# M1705B.net
KiCad netlist of a schematic drawn in EAGLE
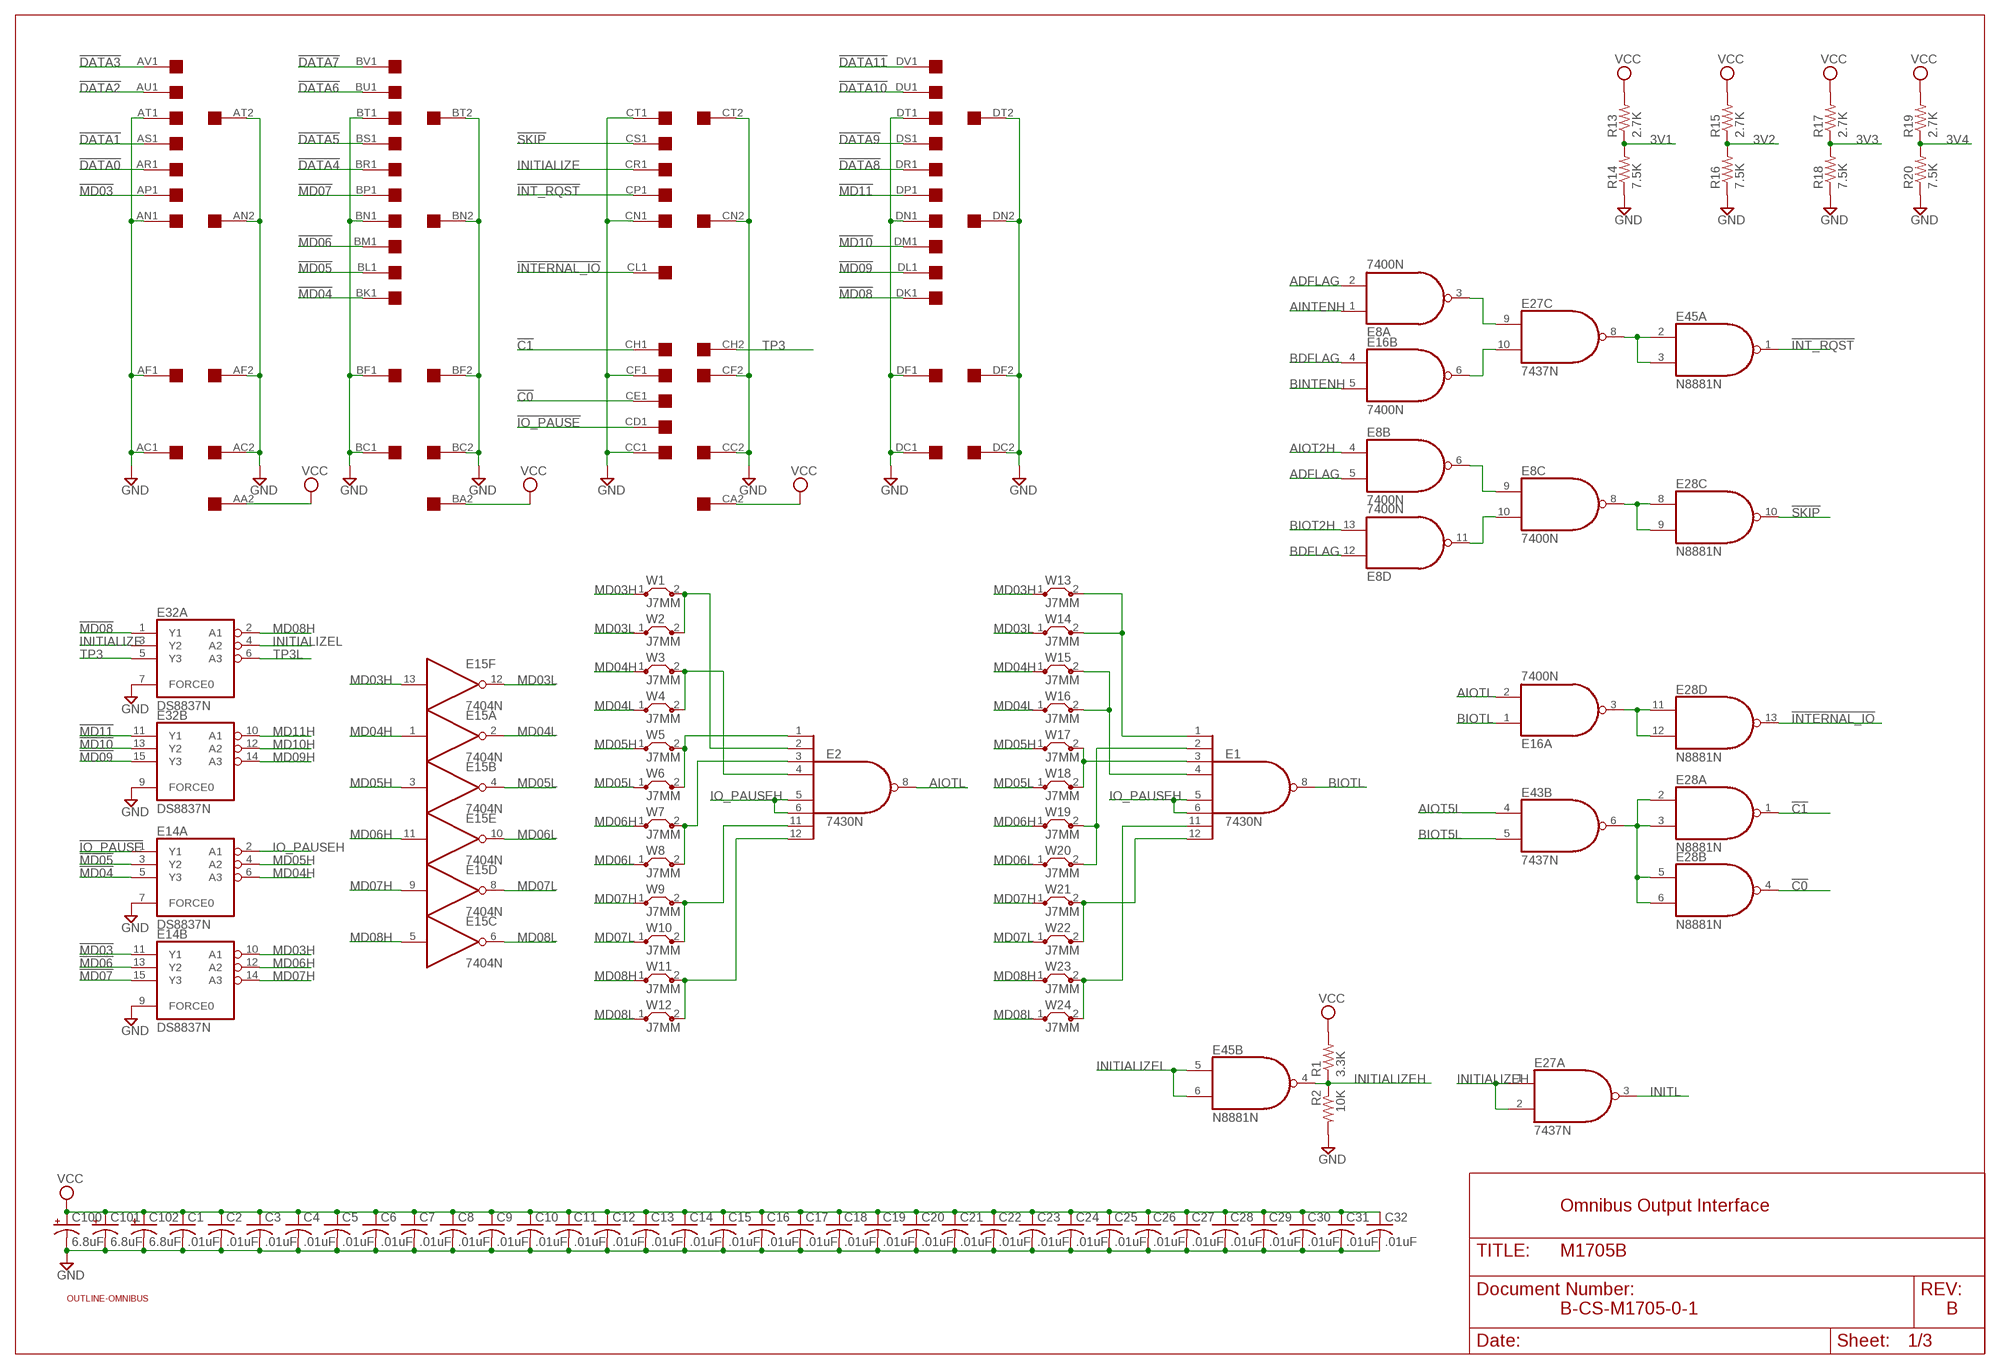
[diagram p0: schematic, sheet 1]
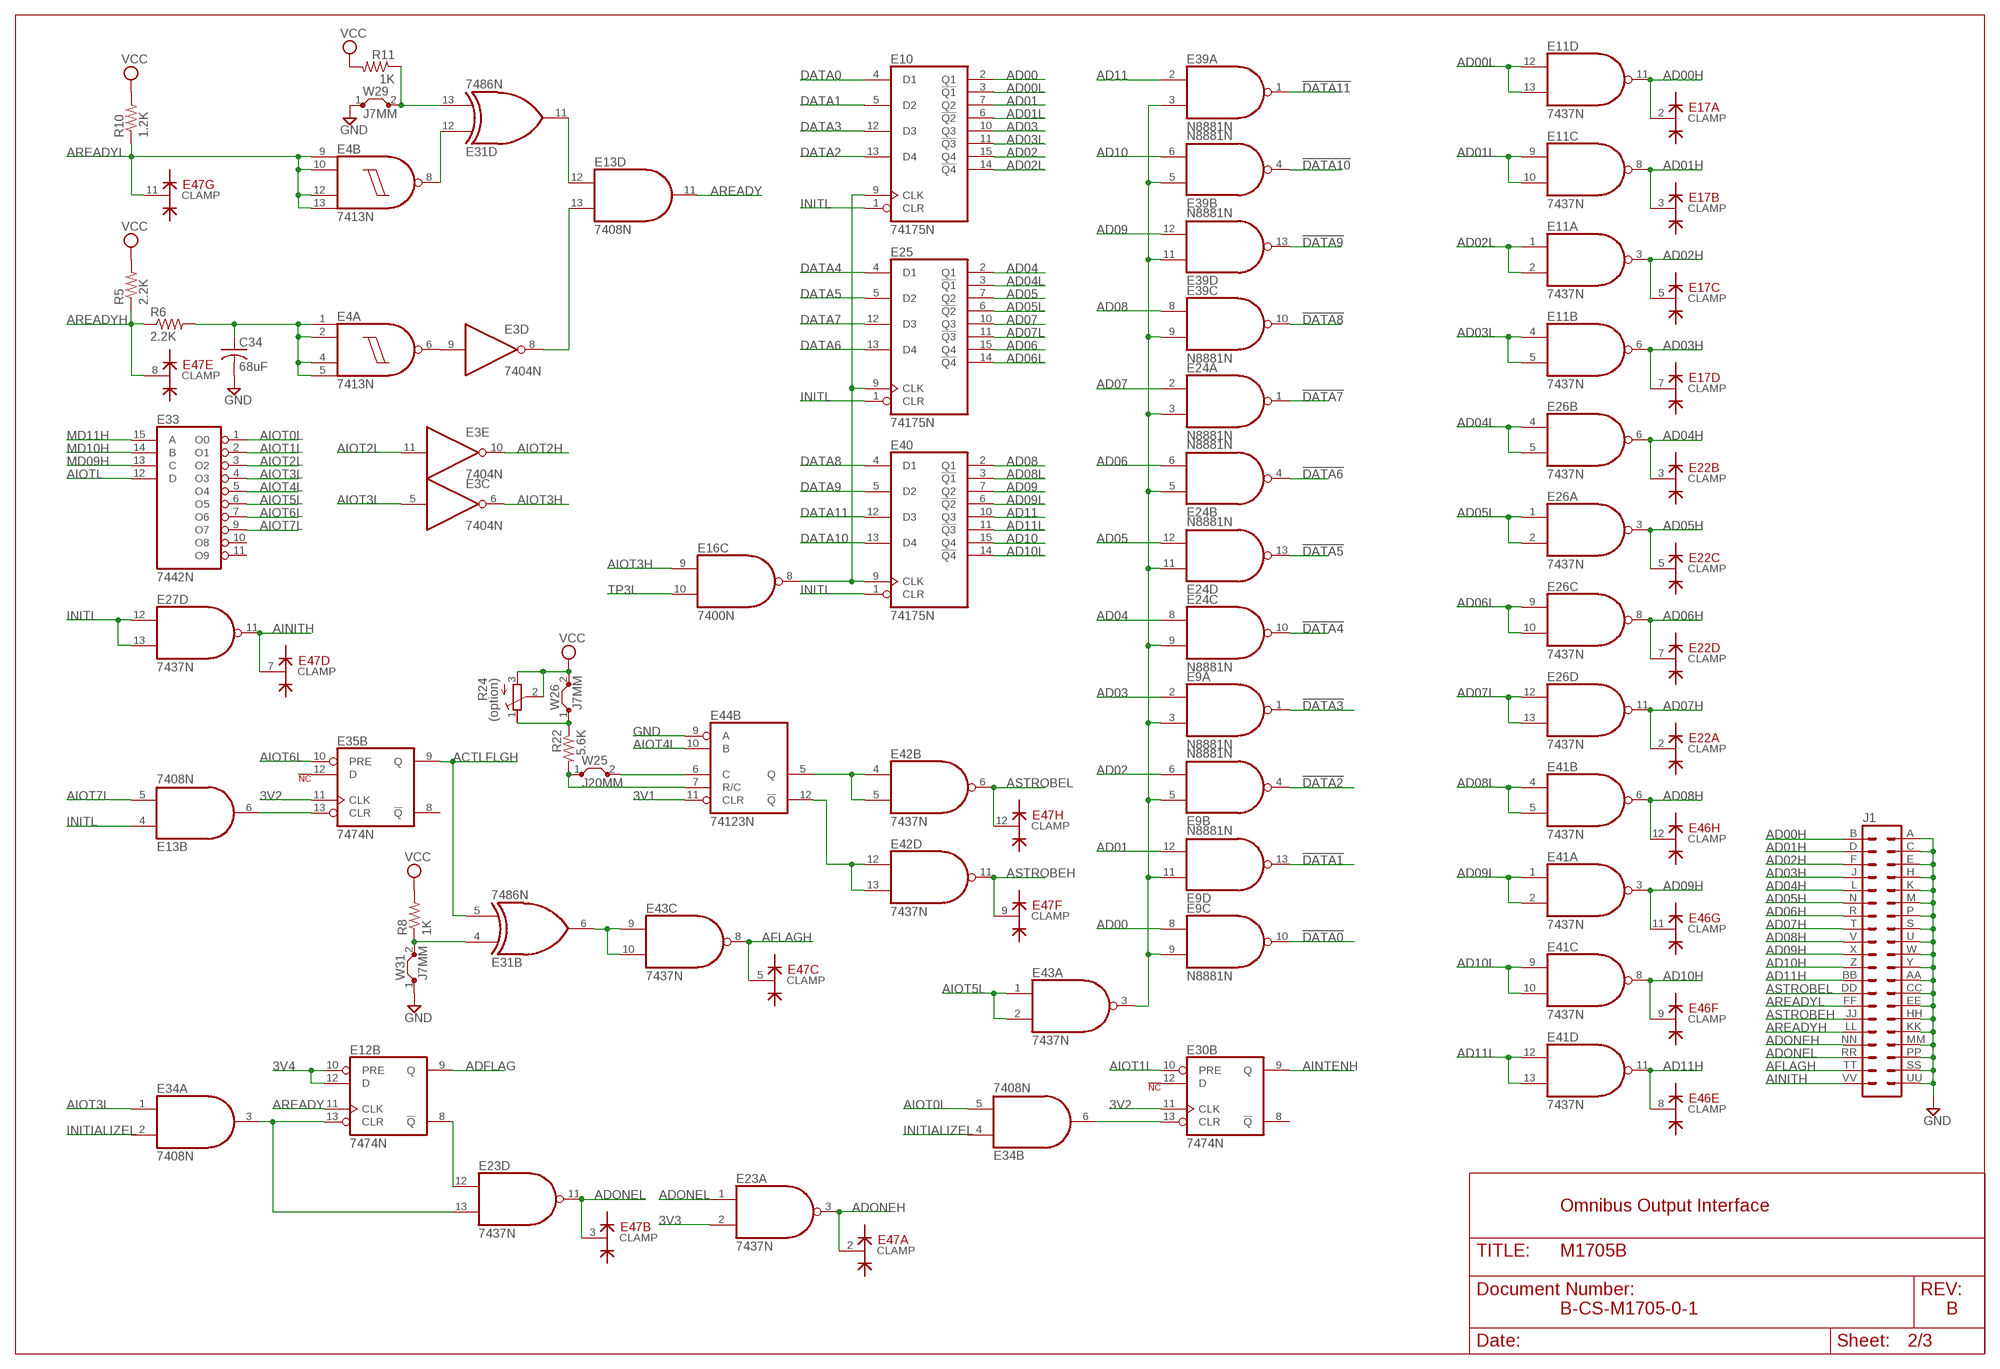
[diagram p1: schematic, sheet 2]
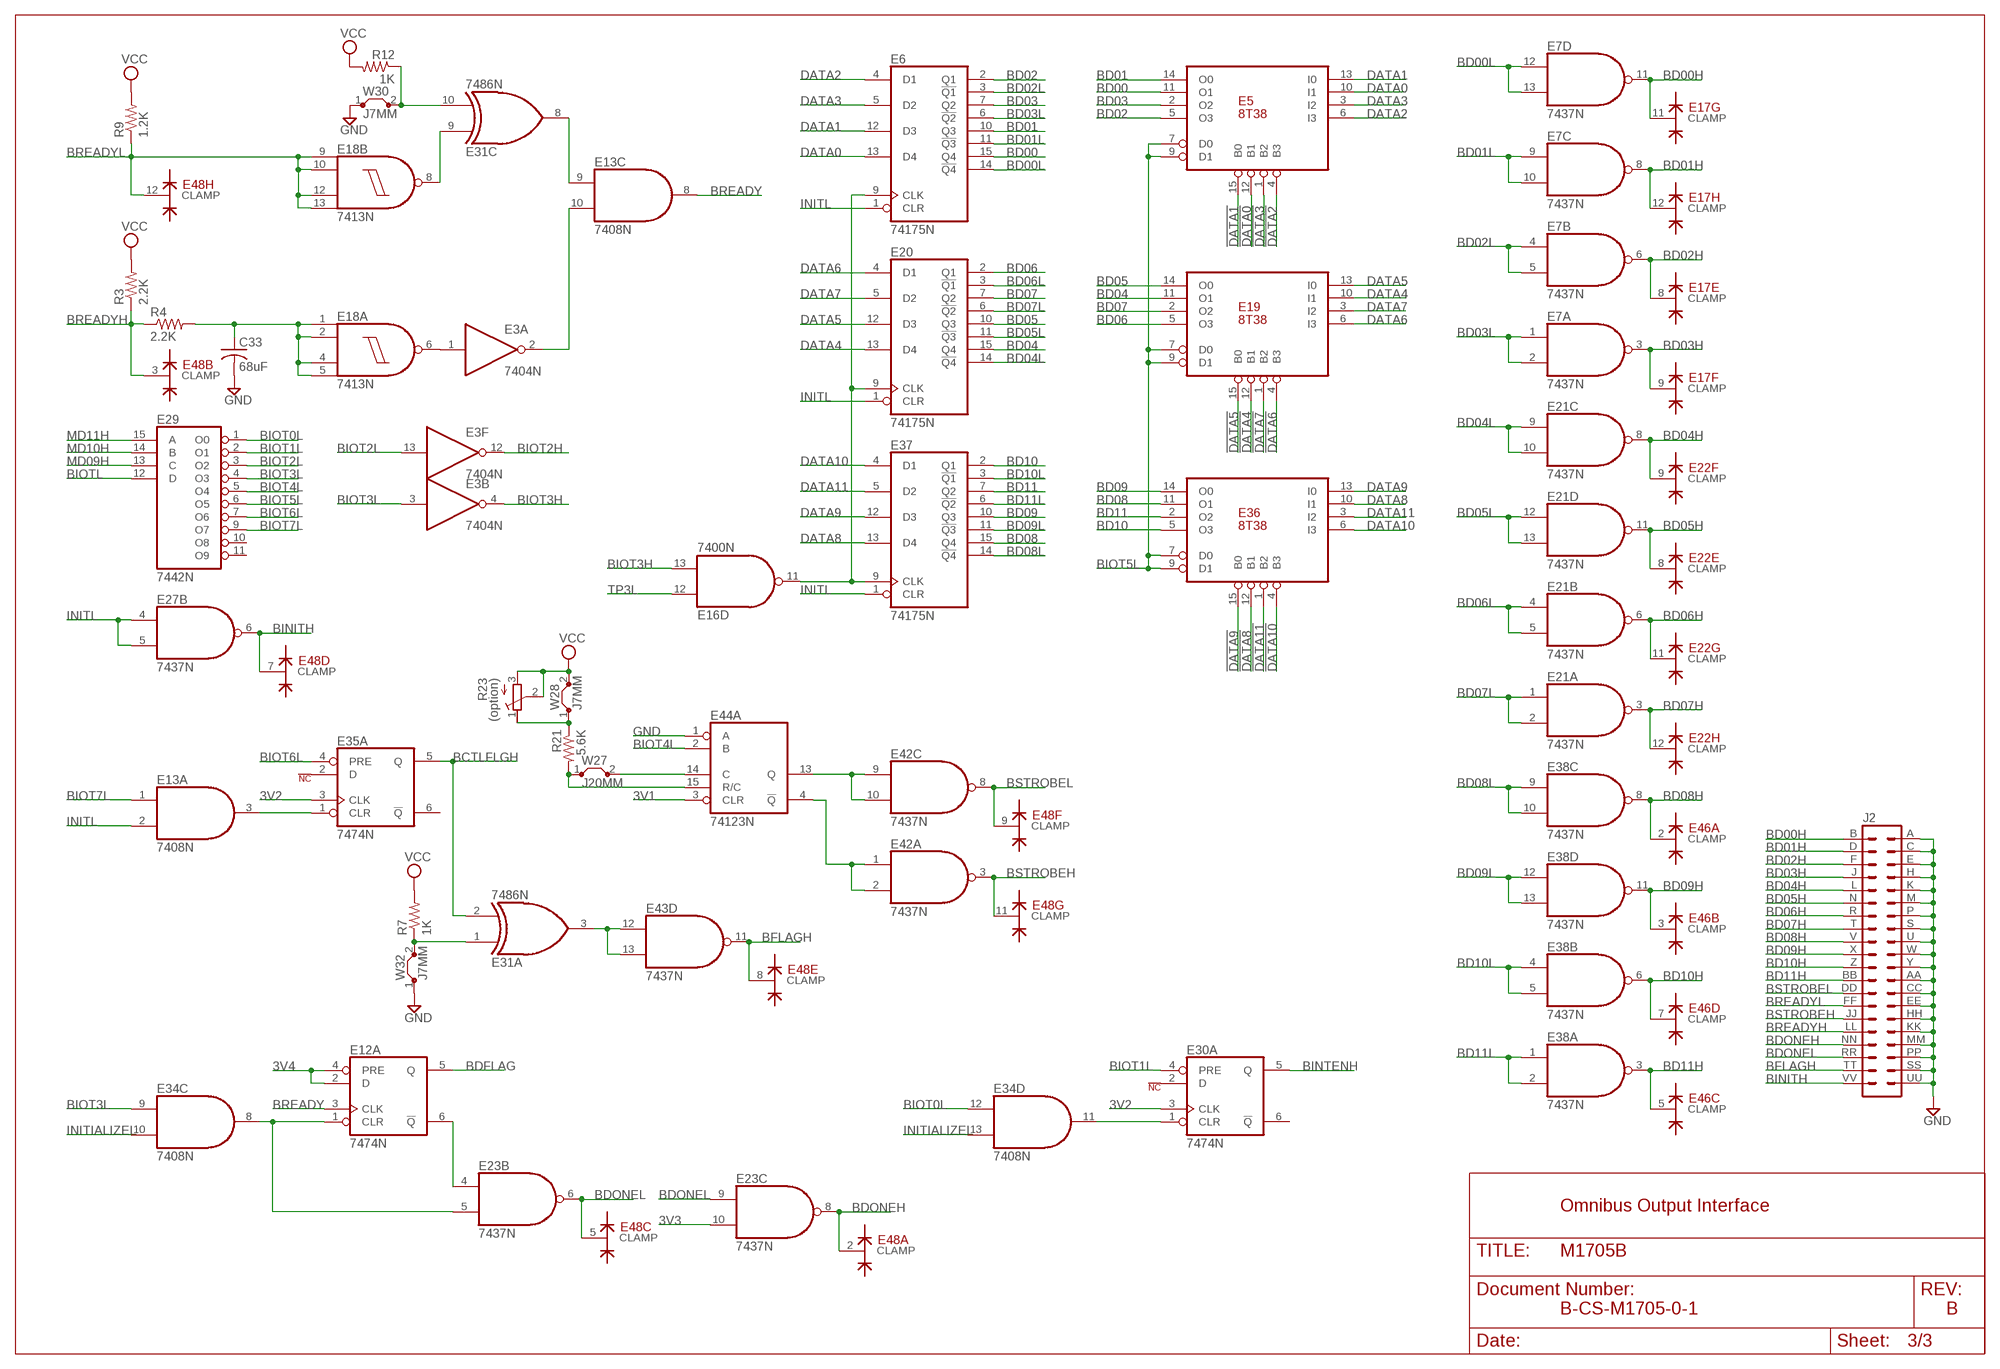
[diagram p2: schematic, sheet 3]

(export (version "E")
  (design (tool "Eeschema 10.0.6"))
  (components
    (comp (ref "C34")
      (value "68uF")
      (footprint "eagle-import:C102-043X133")
      (libsource (lib "eagle-import") (part "C-US102-043X133"))
    )
    (comp (ref "E3")
      (value "7404N")
      (footprint "eagle-import:DIL14")
      (libsource (lib "eagle-import") (part "7404N"))
    )
    (comp (ref "E4")
      (value "7413N")
      (footprint "eagle-import:DIL14")
      (libsource (lib "eagle-import") (part "7413N"))
    )
    (comp (ref "E9")
      (value "N8881N")
      (footprint "eagle-import:DIL14")
      (libsource (lib "eagle-import") (part "N8881N"))
    )
    (comp (ref "E10")
      (value "74175N")
      (footprint "eagle-import:DIL16")
      (libsource (lib "eagle-import") (part "74175N"))
    )
    (comp (ref "E11")
      (value "7437N")
      (footprint "eagle-import:DIL14")
      (libsource (lib "eagle-import") (part "7437N"))
    )
    (comp (ref "E12")
      (value "7474N")
      (footprint "eagle-import:DIL14")
      (libsource (lib "eagle-import") (part "7474NS"))
    )
    (comp (ref "E13")
      (value "7408N")
      (footprint "eagle-import:DIL14")
      (libsource (lib "eagle-import") (part "7408NLS"))
    )
    (comp (ref "E16")
      (value "7400N")
      (footprint "eagle-import:DIL14")
      (libsource (lib "eagle-import") (part "7400N"))
    )
    (comp (ref "E17")
      (value "DEC2501")
      (footprint "eagle-import:DIL14")
      (libsource (lib "eagle-import") (part "DEC2501"))
    )
    (comp (ref "E22")
      (value "DEC2501")
      (footprint "eagle-import:DIL14")
      (libsource (lib "eagle-import") (part "DEC2501"))
    )
    (comp (ref "E23")
      (value "7437N")
      (footprint "eagle-import:DIL14")
      (libsource (lib "eagle-import") (part "7437N"))
    )
    (comp (ref "E24")
      (value "N8881N")
      (footprint "eagle-import:DIL14")
      (libsource (lib "eagle-import") (part "N8881N"))
    )
    (comp (ref "E25")
      (value "74175N")
      (footprint "eagle-import:DIL16")
      (libsource (lib "eagle-import") (part "74175N"))
    )
    (comp (ref "E26")
      (value "7437N")
      (footprint "eagle-import:DIL14")
      (libsource (lib "eagle-import") (part "7437N"))
    )
    (comp (ref "E27")
      (value "7437N")
      (footprint "eagle-import:DIL14")
      (libsource (lib "eagle-import") (part "7437N"))
    )
    (comp (ref "E30")
      (value "7474N")
      (footprint "eagle-import:DIL14")
      (libsource (lib "eagle-import") (part "7474NS"))
    )
    (comp (ref "E31")
      (value "7486N")
      (footprint "eagle-import:DIL14")
      (libsource (lib "eagle-import") (part "7486N"))
    )
    (comp (ref "E33")
      (value "7442N")
      (footprint "eagle-import:DIL16")
      (libsource (lib "eagle-import") (part "7442NLS"))
    )
    (comp (ref "E34")
      (value "7408N")
      (footprint "eagle-import:DIL14")
      (libsource (lib "eagle-import") (part "7408NLS"))
    )
    (comp (ref "E35")
      (value "7474N")
      (footprint "eagle-import:DIL14")
      (libsource (lib "eagle-import") (part "7474NS"))
    )
    (comp (ref "E39")
      (value "N8881N")
      (footprint "eagle-import:DIL14")
      (libsource (lib "eagle-import") (part "N8881N"))
    )
    (comp (ref "E40")
      (value "74175N")
      (footprint "eagle-import:DIL16")
      (libsource (lib "eagle-import") (part "74175N"))
    )
    (comp (ref "E41")
      (value "7437N")
      (footprint "eagle-import:DIL14")
      (libsource (lib "eagle-import") (part "7437N"))
    )
    (comp (ref "E42")
      (value "7437N")
      (footprint "eagle-import:DIL14")
      (libsource (lib "eagle-import") (part "7437N"))
    )
    (comp (ref "E43")
      (value "7437N")
      (footprint "eagle-import:DIL14")
      (libsource (lib "eagle-import") (part "7437N"))
    )
    (comp (ref "E44")
      (value "74123N")
      (footprint "eagle-import:DIL16")
      (libsource (lib "eagle-import") (part "74123N"))
    )
    (comp (ref "E46")
      (value "DEC2501")
      (footprint "eagle-import:DIL14")
      (libsource (lib "eagle-import") (part "DEC2501"))
    )
    (comp (ref "E47")
      (value "DEC2501")
      (footprint "eagle-import:DIL14")
      (libsource (lib "eagle-import") (part "DEC2501"))
    )
    (comp (ref "J1")
      (value "DEC40PINH")
      (footprint "eagle-import:DEC40PINH")
      (libsource (lib "eagle-import") (part "DEC40PINH"))
    )
    (comp (ref "R5")
      (value "2.2K")
      (footprint "eagle-import:0207_10")
      (libsource (lib "eagle-import") (part "R-US_0207/10"))
    )
    (comp (ref "R6")
      (value "2.2K")
      (footprint "eagle-import:0207_10")
      (libsource (lib "eagle-import") (part "R-US_0207/10"))
    )
    (comp (ref "R8")
      (value "1K")
      (footprint "eagle-import:0207_10")
      (libsource (lib "eagle-import") (part "R-US_0207/10"))
    )
    (comp (ref "R10")
      (value "1.2K")
      (footprint "eagle-import:0207_10")
      (libsource (lib "eagle-import") (part "R-US_0207/10"))
    )
    (comp (ref "R11")
      (value "1K")
      (footprint "eagle-import:0207_10")
      (libsource (lib "eagle-import") (part "R-US_0207/10"))
    )
    (comp (ref "R22")
      (value "5.6K")
      (footprint "eagle-import:0207_10")
      (libsource (lib "eagle-import") (part "R-US_0207/10"))
    )
    (comp (ref "R24")
      (value "(option)")
      (footprint "eagle-import:3006Y")
      (libsource (lib "eagle-import") (part "275P"))
    )
    (comp (ref "W25")
      (value "J20MM")
      (footprint "eagle-import:20")
      (libsource (lib "eagle-import") (part "J20MM"))
    )
    (comp (ref "W26")
      (value "J7MM")
      (footprint "eagle-import:07")
      (libsource (lib "eagle-import") (part "J7MM"))
    )
    (comp (ref "W29")
      (value "J7MM")
      (footprint "eagle-import:07")
      (libsource (lib "eagle-import") (part "J7MM"))
    )
    (comp (ref "W31")
      (value "J7MM")
      (footprint "eagle-import:07")
      (libsource (lib "eagle-import") (part "J7MM"))
    )
    (comp (ref "C33")
      (value "68uF")
      (footprint "eagle-import:C102-043X133")
      (libsource (lib "eagle-import") (part "C-US102-043X133"))
    )
    (comp (ref "E5")
      (value "8T38")
      (footprint "eagle-import:DIL16")
      (libsource (lib "eagle-import") (part "DS8641N"))
    )
    (comp (ref "E6")
      (value "74175N")
      (footprint "eagle-import:DIL16")
      (libsource (lib "eagle-import") (part "74175N"))
    )
    (comp (ref "E7")
      (value "7437N")
      (footprint "eagle-import:DIL14")
      (libsource (lib "eagle-import") (part "7437N"))
    )
    (comp (ref "E18")
      (value "7413N")
      (footprint "eagle-import:DIL14")
      (libsource (lib "eagle-import") (part "7413N"))
    )
    (comp (ref "E19")
      (value "8T38")
      (footprint "eagle-import:DIL16")
      (libsource (lib "eagle-import") (part "DS8641N"))
    )
    (comp (ref "E20")
      (value "74175N")
      (footprint "eagle-import:DIL16")
      (libsource (lib "eagle-import") (part "74175N"))
    )
    (comp (ref "E21")
      (value "7437N")
      (footprint "eagle-import:DIL14")
      (libsource (lib "eagle-import") (part "7437N"))
    )
    (comp (ref "E29")
      (value "7442N")
      (footprint "eagle-import:DIL16")
      (libsource (lib "eagle-import") (part "7442NLS"))
    )
    (comp (ref "E36")
      (value "8T38")
      (footprint "eagle-import:DIL16")
      (libsource (lib "eagle-import") (part "DS8641N"))
    )
    (comp (ref "E37")
      (value "74175N")
      (footprint "eagle-import:DIL16")
      (libsource (lib "eagle-import") (part "74175N"))
    )
    (comp (ref "E38")
      (value "7437N")
      (footprint "eagle-import:DIL14")
      (libsource (lib "eagle-import") (part "7437N"))
    )
    (comp (ref "E48")
      (value "DEC2501")
      (footprint "eagle-import:DIL14")
      (libsource (lib "eagle-import") (part "DEC2501"))
    )
    (comp (ref "J2")
      (value "DEC40PINH")
      (footprint "eagle-import:DEC40PINH")
      (libsource (lib "eagle-import") (part "DEC40PINH"))
    )
    (comp (ref "R3")
      (value "2.2K")
      (footprint "eagle-import:0207_10")
      (libsource (lib "eagle-import") (part "R-US_0207/10"))
    )
    (comp (ref "R4")
      (value "2.2K")
      (footprint "eagle-import:0207_10")
      (libsource (lib "eagle-import") (part "R-US_0207/10"))
    )
    (comp (ref "R7")
      (value "1K")
      (footprint "eagle-import:0207_10")
      (libsource (lib "eagle-import") (part "R-US_0207/10"))
    )
    (comp (ref "R9")
      (value "1.2K")
      (footprint "eagle-import:0207_10")
      (libsource (lib "eagle-import") (part "R-US_0207/10"))
    )
    (comp (ref "R12")
      (value "1K")
      (footprint "eagle-import:0207_10")
      (libsource (lib "eagle-import") (part "R-US_0207/10"))
    )
    (comp (ref "R21")
      (value "5.6K")
      (footprint "eagle-import:0207_10")
      (libsource (lib "eagle-import") (part "R-US_0207/10"))
    )
    (comp (ref "R23")
      (value "(option)")
      (footprint "eagle-import:3006Y")
      (libsource (lib "eagle-import") (part "275P"))
    )
    (comp (ref "W27")
      (value "J20MM")
      (footprint "eagle-import:20")
      (libsource (lib "eagle-import") (part "J20MM"))
    )
    (comp (ref "W28")
      (value "J7MM")
      (footprint "eagle-import:07")
      (libsource (lib "eagle-import") (part "J7MM"))
    )
    (comp (ref "W30")
      (value "J7MM")
      (footprint "eagle-import:07")
      (libsource (lib "eagle-import") (part "J7MM"))
    )
    (comp (ref "W32")
      (value "J7MM")
      (footprint "eagle-import:07")
      (libsource (lib "eagle-import") (part "J7MM"))
    )
    (comp (ref "C1")
      (value ".01uF")
      (footprint "eagle-import:C075-032X103")
      (libsource (lib "eagle-import") (part "C-US075-032X103"))
    )
    (comp (ref "C2")
      (value ".01uF")
      (footprint "eagle-import:C075-032X103")
      (libsource (lib "eagle-import") (part "C-US075-032X103"))
    )
    (comp (ref "C3")
      (value ".01uF")
      (footprint "eagle-import:C075-032X103")
      (libsource (lib "eagle-import") (part "C-US075-032X103"))
    )
    (comp (ref "C4")
      (value ".01uF")
      (footprint "eagle-import:C075-032X103")
      (libsource (lib "eagle-import") (part "C-US075-032X103"))
    )
    (comp (ref "C5")
      (value ".01uF")
      (footprint "eagle-import:C075-032X103")
      (libsource (lib "eagle-import") (part "C-US075-032X103"))
    )
    (comp (ref "C6")
      (value ".01uF")
      (footprint "eagle-import:C075-032X103")
      (libsource (lib "eagle-import") (part "C-US075-032X103"))
    )
    (comp (ref "C7")
      (value ".01uF")
      (footprint "eagle-import:C075-032X103")
      (libsource (lib "eagle-import") (part "C-US075-032X103"))
    )
    (comp (ref "C8")
      (value ".01uF")
      (footprint "eagle-import:C075-032X103")
      (libsource (lib "eagle-import") (part "C-US075-032X103"))
    )
    (comp (ref "C9")
      (value ".01uF")
      (footprint "eagle-import:C075-032X103")
      (libsource (lib "eagle-import") (part "C-US075-032X103"))
    )
    (comp (ref "C10")
      (value ".01uF")
      (footprint "eagle-import:C075-032X103")
      (libsource (lib "eagle-import") (part "C-US075-032X103"))
    )
    (comp (ref "C11")
      (value ".01uF")
      (footprint "eagle-import:C075-032X103")
      (libsource (lib "eagle-import") (part "C-US075-032X103"))
    )
    (comp (ref "C12")
      (value ".01uF")
      (footprint "eagle-import:C075-032X103")
      (libsource (lib "eagle-import") (part "C-US075-032X103"))
    )
    (comp (ref "C13")
      (value ".01uF")
      (footprint "eagle-import:C075-032X103")
      (libsource (lib "eagle-import") (part "C-US075-032X103"))
    )
    (comp (ref "C14")
      (value ".01uF")
      (footprint "eagle-import:C075-032X103")
      (libsource (lib "eagle-import") (part "C-US075-032X103"))
    )
    (comp (ref "C15")
      (value ".01uF")
      (footprint "eagle-import:C075-032X103")
      (libsource (lib "eagle-import") (part "C-US075-032X103"))
    )
    (comp (ref "C16")
      (value ".01uF")
      (footprint "eagle-import:C075-032X103")
      (libsource (lib "eagle-import") (part "C-US075-032X103"))
    )
    (comp (ref "C17")
      (value ".01uF")
      (footprint "eagle-import:C075-032X103")
      (libsource (lib "eagle-import") (part "C-US075-032X103"))
    )
    (comp (ref "C18")
      (value ".01uF")
      (footprint "eagle-import:C075-032X103")
      (libsource (lib "eagle-import") (part "C-US075-032X103"))
    )
    (comp (ref "C19")
      (value ".01uF")
      (footprint "eagle-import:C075-032X103")
      (libsource (lib "eagle-import") (part "C-US075-032X103"))
    )
    (comp (ref "C20")
      (value ".01uF")
      (footprint "eagle-import:C075-032X103")
      (libsource (lib "eagle-import") (part "C-US075-032X103"))
    )
    (comp (ref "C21")
      (value ".01uF")
      (footprint "eagle-import:C075-032X103")
      (libsource (lib "eagle-import") (part "C-US075-032X103"))
    )
    (comp (ref "C22")
      (value ".01uF")
      (footprint "eagle-import:C075-032X103")
      (libsource (lib "eagle-import") (part "C-US075-032X103"))
    )
    (comp (ref "C23")
      (value ".01uF")
      (footprint "eagle-import:C075-032X103")
      (libsource (lib "eagle-import") (part "C-US075-032X103"))
    )
    (comp (ref "C24")
      (value ".01uF")
      (footprint "eagle-import:C075-032X103")
      (libsource (lib "eagle-import") (part "C-US075-032X103"))
    )
    (comp (ref "C25")
      (value ".01uF")
      (footprint "eagle-import:C075-032X103")
      (libsource (lib "eagle-import") (part "C-US075-032X103"))
    )
    (comp (ref "C26")
      (value ".01uF")
      (footprint "eagle-import:C075-032X103")
      (libsource (lib "eagle-import") (part "C-US075-032X103"))
    )
    (comp (ref "C27")
      (value ".01uF")
      (footprint "eagle-import:C075-032X103")
      (libsource (lib "eagle-import") (part "C-US075-032X103"))
    )
    (comp (ref "C28")
      (value ".01uF")
      (footprint "eagle-import:C075-032X103")
      (libsource (lib "eagle-import") (part "C-US075-032X103"))
    )
    (comp (ref "C29")
      (value ".01uF")
      (footprint "eagle-import:C075-032X103")
      (libsource (lib "eagle-import") (part "C-US075-032X103"))
    )
    (comp (ref "C30")
      (value ".01uF")
      (footprint "eagle-import:C075-032X103")
      (libsource (lib "eagle-import") (part "C-US075-032X103"))
    )
    (comp (ref "C31")
      (value ".01uF")
      (footprint "eagle-import:C075-032X103")
      (libsource (lib "eagle-import") (part "C-US075-032X103"))
    )
    (comp (ref "C32")
      (value ".01uF")
      (footprint "eagle-import:C075-032X103")
      (libsource (lib "eagle-import") (part "C-US075-032X103"))
    )
    (comp (ref "C100")
      (value "6.8uF")
      (footprint "eagle-import:E12-8")
      (libsource (lib "eagle-import") (part "CPOL-USE20-8AXIAL"))
    )
    (comp (ref "C101")
      (value "6.8uF")
      (footprint "eagle-import:E12-8")
      (libsource (lib "eagle-import") (part "CPOL-USE20-8AXIAL"))
    )
    (comp (ref "C102")
      (value "6.8uF")
      (footprint "eagle-import:E12-8")
      (libsource (lib "eagle-import") (part "CPOL-USE20-8AXIAL"))
    )
    (comp (ref "E1")
      (value "7430N")
      (footprint "eagle-import:DIL14")
      (libsource (lib "eagle-import") (part "7430N"))
    )
    (comp (ref "E2")
      (value "7430N")
      (footprint "eagle-import:DIL14")
      (libsource (lib "eagle-import") (part "7430N"))
    )
    (comp (ref "E8")
      (value "7400N")
      (footprint "eagle-import:DIL14")
      (libsource (lib "eagle-import") (part "7400N"))
    )
    (comp (ref "E14")
      (value "DS8837N")
      (footprint "eagle-import:DIL16")
      (libsource (lib "eagle-import") (part "DS8837N"))
    )
    (comp (ref "E15")
      (value "7404N")
      (footprint "eagle-import:DIL14")
      (libsource (lib "eagle-import") (part "7404N"))
    )
    (comp (ref "E28")
      (value "N8881N")
      (footprint "eagle-import:DIL14")
      (libsource (lib "eagle-import") (part "N8881N"))
    )
    (comp (ref "E32")
      (value "DS8837N")
      (footprint "eagle-import:DIL16")
      (libsource (lib "eagle-import") (part "DS8837N"))
    )
    (comp (ref "E45")
      (value "N8881N")
      (footprint "eagle-import:DIL14")
      (libsource (lib "eagle-import") (part "N8881N"))
    )
    (comp (ref "R1")
      (value "3.3K")
      (footprint "eagle-import:0207_10")
      (libsource (lib "eagle-import") (part "R-US_0207/10"))
    )
    (comp (ref "R2")
      (value "10K")
      (footprint "eagle-import:0207_10")
      (libsource (lib "eagle-import") (part "R-US_0207/10"))
    )
    (comp (ref "R13")
      (value "2.7K")
      (footprint "eagle-import:0207_10")
      (libsource (lib "eagle-import") (part "R-US_0207/10"))
    )
    (comp (ref "R14")
      (value "7.5K")
      (footprint "eagle-import:0207_10")
      (libsource (lib "eagle-import") (part "R-US_0207/10"))
    )
    (comp (ref "R15")
      (value "2.7K")
      (footprint "eagle-import:0207_10")
      (libsource (lib "eagle-import") (part "R-US_0207/10"))
    )
    (comp (ref "R16")
      (value "7.5K")
      (footprint "eagle-import:0207_10")
      (libsource (lib "eagle-import") (part "R-US_0207/10"))
    )
    (comp (ref "R17")
      (value "2.7K")
      (footprint "eagle-import:0207_10")
      (libsource (lib "eagle-import") (part "R-US_0207/10"))
    )
    (comp (ref "R18")
      (value "7.5K")
      (footprint "eagle-import:0207_10")
      (libsource (lib "eagle-import") (part "R-US_0207/10"))
    )
    (comp (ref "R19")
      (value "2.7K")
      (footprint "eagle-import:0207_10")
      (libsource (lib "eagle-import") (part "R-US_0207/10"))
    )
    (comp (ref "R20")
      (value "7.5K")
      (footprint "eagle-import:0207_10")
      (libsource (lib "eagle-import") (part "R-US_0207/10"))
    )
    (comp (ref "U$2")
      (value "QUAD")
      (footprint "eagle-import:EDGE-CON8")
      (libsource (lib "eagle-import") (part "QUAD"))
    )
    (comp (ref "U$4")
      (value "OUTLINE-OMNIBUS")
      (footprint "eagle-import:OMNIBUS")
      (libsource (lib "eagle-import") (part "OUTLINE-OMNIBUS"))
    )
    (comp (ref "W1")
      (value "J7MM")
      (footprint "eagle-import:07")
      (libsource (lib "eagle-import") (part "J7MM"))
    )
    (comp (ref "W2")
      (value "J7MM")
      (footprint "eagle-import:07")
      (libsource (lib "eagle-import") (part "J7MM"))
    )
    (comp (ref "W3")
      (value "J7MM")
      (footprint "eagle-import:07")
      (libsource (lib "eagle-import") (part "J7MM"))
    )
    (comp (ref "W4")
      (value "J7MM")
      (footprint "eagle-import:07")
      (libsource (lib "eagle-import") (part "J7MM"))
    )
    (comp (ref "W5")
      (value "J7MM")
      (footprint "eagle-import:07")
      (libsource (lib "eagle-import") (part "J7MM"))
    )
    (comp (ref "W6")
      (value "J7MM")
      (footprint "eagle-import:07")
      (libsource (lib "eagle-import") (part "J7MM"))
    )
    (comp (ref "W7")
      (value "J7MM")
      (footprint "eagle-import:07")
      (libsource (lib "eagle-import") (part "J7MM"))
    )
    (comp (ref "W8")
      (value "J7MM")
      (footprint "eagle-import:07")
      (libsource (lib "eagle-import") (part "J7MM"))
    )
    (comp (ref "W9")
      (value "J7MM")
      (footprint "eagle-import:07")
      (libsource (lib "eagle-import") (part "J7MM"))
    )
    (comp (ref "W10")
      (value "J7MM")
      (footprint "eagle-import:07")
      (libsource (lib "eagle-import") (part "J7MM"))
    )
    (comp (ref "W11")
      (value "J7MM")
      (footprint "eagle-import:07")
      (libsource (lib "eagle-import") (part "J7MM"))
    )
    (comp (ref "W12")
      (value "J7MM")
      (footprint "eagle-import:07")
      (libsource (lib "eagle-import") (part "J7MM"))
    )
    (comp (ref "W13")
      (value "J7MM")
      (footprint "eagle-import:07")
      (libsource (lib "eagle-import") (part "J7MM"))
    )
    (comp (ref "W14")
      (value "J7MM")
      (footprint "eagle-import:07")
      (libsource (lib "eagle-import") (part "J7MM"))
    )
    (comp (ref "W15")
      (value "J7MM")
      (footprint "eagle-import:07")
      (libsource (lib "eagle-import") (part "J7MM"))
    )
    (comp (ref "W16")
      (value "J7MM")
      (footprint "eagle-import:07")
      (libsource (lib "eagle-import") (part "J7MM"))
    )
    (comp (ref "W17")
      (value "J7MM")
      (footprint "eagle-import:07")
      (libsource (lib "eagle-import") (part "J7MM"))
    )
    (comp (ref "W18")
      (value "J7MM")
      (footprint "eagle-import:07")
      (libsource (lib "eagle-import") (part "J7MM"))
    )
    (comp (ref "W19")
      (value "J7MM")
      (footprint "eagle-import:07")
      (libsource (lib "eagle-import") (part "J7MM"))
    )
    (comp (ref "W20")
      (value "J7MM")
      (footprint "eagle-import:07")
      (libsource (lib "eagle-import") (part "J7MM"))
    )
    (comp (ref "W21")
      (value "J7MM")
      (footprint "eagle-import:07")
      (libsource (lib "eagle-import") (part "J7MM"))
    )
    (comp (ref "W22")
      (value "J7MM")
      (footprint "eagle-import:07")
      (libsource (lib "eagle-import") (part "J7MM"))
    )
    (comp (ref "W23")
      (value "J7MM")
      (footprint "eagle-import:07")
      (libsource (lib "eagle-import") (part "J7MM"))
    )
    (comp (ref "W24")
      (value "J7MM")
      (footprint "eagle-import:07")
      (libsource (lib "eagle-import") (part "J7MM"))
    )
  )
  (nets
    (net (code "1") (name "3V1") (class "Default")
      (node (ref "E44") (pin "11") (pinfunction "CLR_11") (pintype "input"))
      (node (ref "E44") (pin "3") (pinfunction "CLR_3") (pintype "input"))
      (node (ref "R13") (pin "1") (pinfunction "1_1") (pintype "passive"))
      (node (ref "R14") (pin "2") (pinfunction "2_2") (pintype "passive"))
    )
    (net (code "2") (name "3V2") (class "Default")
      (node (ref "E30") (pin "11") (pinfunction "CLK_11") (pintype "input"))
      (node (ref "E30") (pin "3") (pinfunction "CLK_3") (pintype "input"))
      (node (ref "E35") (pin "11") (pinfunction "CLK_11") (pintype "input"))
      (node (ref "E35") (pin "3") (pinfunction "CLK_3") (pintype "input"))
      (node (ref "R15") (pin "1") (pinfunction "1_1") (pintype "passive"))
      (node (ref "R16") (pin "2") (pinfunction "2_2") (pintype "passive"))
    )
    (net (code "3") (name "3V3") (class "Default")
      (node (ref "E23") (pin "10") (pinfunction "I1_10") (pintype "input"))
      (node (ref "E23") (pin "2") (pinfunction "I1_2") (pintype "input"))
      (node (ref "R17") (pin "1") (pinfunction "1_1") (pintype "passive"))
      (node (ref "R18") (pin "2") (pinfunction "2_2") (pintype "passive"))
    )
    (net (code "4") (name "3V4") (class "Default")
      (node (ref "E12") (pin "10") (pinfunction "PRE_10") (pintype "input"))
      (node (ref "E12") (pin "12") (pinfunction "D_12") (pintype "input"))
      (node (ref "E12") (pin "2") (pinfunction "D_2") (pintype "input"))
      (node (ref "E12") (pin "4") (pinfunction "PRE_4") (pintype "input"))
      (node (ref "R19") (pin "1") (pinfunction "1_1") (pintype "passive"))
      (node (ref "R20") (pin "2") (pinfunction "2_2") (pintype "passive"))
    )
    (net (code "5") (name "ACTLFLGH") (class "Default")
      (node (ref "E31") (pin "5") (pinfunction "I1_5") (pintype "input"))
      (node (ref "E35") (pin "9") (pinfunction "Q_9") (pintype "output"))
    )
    (net (code "6") (name "AD00") (class "Default")
      (node (ref "E10") (pin "2") (pinfunction "Q1_2") (pintype "output"))
      (node (ref "E9") (pin "8") (pinfunction "I0_8") (pintype "input"))
    )
    (net (code "7") (name "AD00H") (class "Default")
      (node (ref "E11") (pin "11") (pinfunction "O_11") (pintype "output"))
      (node (ref "E17") (pin "2") (pinfunction "CLAMP_2") (pintype "input"))
      (node (ref "J1") (pin "B") (pinfunction "2_B") (pintype "bidirectional"))
    )
    (net (code "8") (name "AD00L") (class "Default")
      (node (ref "E10") (pin "3") (pinfunction "~{Q1}_3") (pintype "output"))
      (node (ref "E11") (pin "12") (pinfunction "I0_12") (pintype "input"))
      (node (ref "E11") (pin "13") (pinfunction "I1_13") (pintype "input"))
    )
    (net (code "9") (name "AD01") (class "Default")
      (node (ref "E10") (pin "7") (pinfunction "Q2_7") (pintype "output"))
      (node (ref "E9") (pin "12") (pinfunction "I1_12") (pintype "input"))
    )
    (net (code "10") (name "AD01H") (class "Default")
      (node (ref "E11") (pin "8") (pinfunction "O_8") (pintype "output"))
      (node (ref "E17") (pin "3") (pinfunction "CLAMP_3") (pintype "input"))
      (node (ref "J1") (pin "D") (pinfunction "4_D") (pintype "bidirectional"))
    )
    (net (code "11") (name "AD01L") (class "Default")
      (node (ref "E10") (pin "6") (pinfunction "~{Q2}_6") (pintype "output"))
      (node (ref "E11") (pin "10") (pinfunction "I1_10") (pintype "input"))
      (node (ref "E11") (pin "9") (pinfunction "I0_9") (pintype "input"))
    )
    (net (code "12") (name "AD02") (class "Default")
      (node (ref "E10") (pin "15") (pinfunction "Q4_15") (pintype "output"))
      (node (ref "E9") (pin "6") (pinfunction "I1_6") (pintype "input"))
    )
    (net (code "13") (name "AD02H") (class "Default")
      (node (ref "E11") (pin "3") (pinfunction "O_3") (pintype "output"))
      (node (ref "E17") (pin "5") (pinfunction "CLAMP_5") (pintype "input"))
      (node (ref "J1") (pin "F") (pinfunction "6_F") (pintype "bidirectional"))
    )
    (net (code "14") (name "AD02L") (class "Default")
      (node (ref "E10") (pin "14") (pinfunction "~{Q4}_14") (pintype "output"))
      (node (ref "E11") (pin "1") (pinfunction "I0_1") (pintype "input"))
      (node (ref "E11") (pin "2") (pinfunction "I1_2") (pintype "input"))
    )
    (net (code "15") (name "AD03") (class "Default")
      (node (ref "E10") (pin "10") (pinfunction "Q3_10") (pintype "output"))
      (node (ref "E9") (pin "2") (pinfunction "I0_2") (pintype "input"))
    )
    (net (code "16") (name "AD03H") (class "Default")
      (node (ref "E11") (pin "6") (pinfunction "O_6") (pintype "output"))
      (node (ref "E17") (pin "7") (pinfunction "CLAMP_7") (pintype "input"))
      (node (ref "J1") (pin "J") (pinfunction "8_J") (pintype "bidirectional"))
    )
    (net (code "17") (name "AD03L") (class "Default")
      (node (ref "E10") (pin "11") (pinfunction "~{Q3}_11") (pintype "output"))
      (node (ref "E11") (pin "4") (pinfunction "I0_4") (pintype "input"))
      (node (ref "E11") (pin "5") (pinfunction "I1_5") (pintype "input"))
    )
    (net (code "18") (name "AD04") (class "Default")
      (node (ref "E24") (pin "8") (pinfunction "I0_8") (pintype "input"))
      (node (ref "E25") (pin "2") (pinfunction "Q1_2") (pintype "output"))
    )
    (net (code "19") (name "AD04H") (class "Default")
      (node (ref "E22") (pin "3") (pinfunction "CLAMP_3") (pintype "input"))
      (node (ref "E26") (pin "6") (pinfunction "O_6") (pintype "output"))
      (node (ref "J1") (pin "L") (pinfunction "10_L") (pintype "bidirectional"))
    )
    (net (code "20") (name "AD04L") (class "Default")
      (node (ref "E25") (pin "3") (pinfunction "~{Q1}_3") (pintype "output"))
      (node (ref "E26") (pin "4") (pinfunction "I0_4") (pintype "input"))
      (node (ref "E26") (pin "5") (pinfunction "I1_5") (pintype "input"))
    )
    (net (code "21") (name "AD05") (class "Default")
      (node (ref "E24") (pin "12") (pinfunction "I1_12") (pintype "input"))
      (node (ref "E25") (pin "7") (pinfunction "Q2_7") (pintype "output"))
    )
    (net (code "22") (name "AD05H") (class "Default")
      (node (ref "E22") (pin "5") (pinfunction "CLAMP_5") (pintype "input"))
      (node (ref "E26") (pin "3") (pinfunction "O_3") (pintype "output"))
      (node (ref "J1") (pin "N") (pinfunction "12_N") (pintype "bidirectional"))
    )
    (net (code "23") (name "AD05L") (class "Default")
      (node (ref "E25") (pin "6") (pinfunction "~{Q2}_6") (pintype "output"))
      (node (ref "E26") (pin "1") (pinfunction "I0_1") (pintype "input"))
      (node (ref "E26") (pin "2") (pinfunction "I1_2") (pintype "input"))
    )
    (net (code "24") (name "AD06") (class "Default")
      (node (ref "E24") (pin "6") (pinfunction "I1_6") (pintype "input"))
      (node (ref "E25") (pin "15") (pinfunction "Q4_15") (pintype "output"))
    )
    (net (code "25") (name "AD06H") (class "Default")
      (node (ref "E22") (pin "7") (pinfunction "CLAMP_7") (pintype "input"))
      (node (ref "E26") (pin "8") (pinfunction "O_8") (pintype "output"))
      (node (ref "J1") (pin "R") (pinfunction "14_R") (pintype "bidirectional"))
    )
    (net (code "26") (name "AD06L") (class "Default")
      (node (ref "E25") (pin "14") (pinfunction "~{Q4}_14") (pintype "output"))
      (node (ref "E26") (pin "10") (pinfunction "I1_10") (pintype "input"))
      (node (ref "E26") (pin "9") (pinfunction "I0_9") (pintype "input"))
    )
    (net (code "27") (name "AD07") (class "Default")
      (node (ref "E24") (pin "2") (pinfunction "I0_2") (pintype "input"))
      (node (ref "E25") (pin "10") (pinfunction "Q3_10") (pintype "output"))
    )
    (net (code "28") (name "AD07H") (class "Default")
      (node (ref "E22") (pin "2") (pinfunction "CLAMP_2") (pintype "input"))
      (node (ref "E26") (pin "11") (pinfunction "O_11") (pintype "output"))
      (node (ref "J1") (pin "T") (pinfunction "16_T") (pintype "bidirectional"))
    )
    (net (code "29") (name "AD07L") (class "Default")
      (node (ref "E25") (pin "11") (pinfunction "~{Q3}_11") (pintype "output"))
      (node (ref "E26") (pin "12") (pinfunction "I0_12") (pintype "input"))
      (node (ref "E26") (pin "13") (pinfunction "I1_13") (pintype "input"))
    )
    (net (code "30") (name "AD08") (class "Default")
      (node (ref "E39") (pin "8") (pinfunction "I0_8") (pintype "input"))
      (node (ref "E40") (pin "2") (pinfunction "Q1_2") (pintype "output"))
    )
    (net (code "31") (name "AD08H") (class "Default")
      (node (ref "E41") (pin "6") (pinfunction "O_6") (pintype "output"))
      (node (ref "E46") (pin "12") (pinfunction "CLAMP_12") (pintype "input"))
      (node (ref "J1") (pin "V") (pinfunction "18_V") (pintype "bidirectional"))
    )
    (net (code "32") (name "AD08L") (class "Default")
      (node (ref "E40") (pin "3") (pinfunction "~{Q1}_3") (pintype "output"))
      (node (ref "E41") (pin "4") (pinfunction "I0_4") (pintype "input"))
      (node (ref "E41") (pin "5") (pinfunction "I1_5") (pintype "input"))
    )
    (net (code "33") (name "AD09") (class "Default")
      (node (ref "E39") (pin "12") (pinfunction "I1_12") (pintype "input"))
      (node (ref "E40") (pin "7") (pinfunction "Q2_7") (pintype "output"))
    )
    (net (code "34") (name "AD09H") (class "Default")
      (node (ref "E41") (pin "3") (pinfunction "O_3") (pintype "output"))
      (node (ref "E46") (pin "11") (pinfunction "CLAMP_11") (pintype "input"))
      (node (ref "J1") (pin "X") (pinfunction "20_X") (pintype "bidirectional"))
    )
    (net (code "35") (name "AD09L") (class "Default")
      (node (ref "E40") (pin "6") (pinfunction "~{Q2}_6") (pintype "output"))
      (node (ref "E41") (pin "1") (pinfunction "I0_1") (pintype "input"))
      (node (ref "E41") (pin "2") (pinfunction "I1_2") (pintype "input"))
    )
    (net (code "36") (name "AD10") (class "Default")
      (node (ref "E39") (pin "6") (pinfunction "I1_6") (pintype "input"))
      (node (ref "E40") (pin "15") (pinfunction "Q4_15") (pintype "output"))
    )
    (net (code "37") (name "AD10H") (class "Default")
      (node (ref "E41") (pin "8") (pinfunction "O_8") (pintype "output"))
      (node (ref "E46") (pin "9") (pinfunction "CLAMP_9") (pintype "input"))
      (node (ref "J1") (pin "Z") (pinfunction "22_Z") (pintype "bidirectional"))
    )
    (net (code "38") (name "AD10L") (class "Default")
      (node (ref "E40") (pin "14") (pinfunction "~{Q4}_14") (pintype "output"))
      (node (ref "E41") (pin "10") (pinfunction "I1_10") (pintype "input"))
      (node (ref "E41") (pin "9") (pinfunction "I0_9") (pintype "input"))
    )
    (net (code "39") (name "AD11") (class "Default")
      (node (ref "E39") (pin "2") (pinfunction "I0_2") (pintype "input"))
      (node (ref "E40") (pin "10") (pinfunction "Q3_10") (pintype "output"))
    )
    (net (code "40") (name "AD11H") (class "Default")
      (node (ref "E41") (pin "11") (pinfunction "O_11") (pintype "output"))
      (node (ref "E46") (pin "8") (pinfunction "CLAMP_8") (pintype "input"))
      (node (ref "J1") (pin "BB") (pinfunction "24_BB") (pintype "bidirectional"))
    )
    (net (code "41") (name "AD11L") (class "Default")
      (node (ref "E40") (pin "11") (pinfunction "~{Q3}_11") (pintype "output"))
      (node (ref "E41") (pin "12") (pinfunction "I0_12") (pintype "input"))
      (node (ref "E41") (pin "13") (pinfunction "I1_13") (pintype "input"))
    )
    (net (code "42") (name "ADFLAG") (class "Default")
      (node (ref "E12") (pin "9") (pinfunction "Q_9") (pintype "output"))
      (node (ref "E8") (pin "2") (pinfunction "I1_2") (pintype "input"))
      (node (ref "E8") (pin "5") (pinfunction "I1_5") (pintype "input"))
    )
    (net (code "43") (name "ADONEH") (class "Default")
      (node (ref "E23") (pin "3") (pinfunction "O_3") (pintype "output"))
      (node (ref "E47") (pin "2") (pinfunction "CLAMP_2") (pintype "input"))
      (node (ref "J1") (pin "NN") (pinfunction "34_NN") (pintype "bidirectional"))
    )
    (net (code "44") (name "ADONEL") (class "Default")
      (node (ref "E23") (pin "1") (pinfunction "I0_1") (pintype "input"))
      (node (ref "E23") (pin "11") (pinfunction "O_11") (pintype "output"))
      (node (ref "E47") (pin "3") (pinfunction "CLAMP_3") (pintype "input"))
      (node (ref "J1") (pin "RR") (pinfunction "36_RR") (pintype "bidirectional"))
    )
    (net (code "45") (name "AFLAGH") (class "Default")
      (node (ref "E43") (pin "8") (pinfunction "O_8") (pintype "output"))
      (node (ref "E47") (pin "5") (pinfunction "CLAMP_5") (pintype "input"))
      (node (ref "J1") (pin "TT") (pinfunction "38_TT") (pintype "bidirectional"))
    )
    (net (code "46") (name "AINITH") (class "Default")
      (node (ref "E27") (pin "11") (pinfunction "O_11") (pintype "output"))
      (node (ref "E47") (pin "7") (pinfunction "CLAMP_7") (pintype "input"))
      (node (ref "J1") (pin "VV") (pinfunction "40_VV") (pintype "bidirectional"))
    )
    (net (code "47") (name "AINTENH") (class "Default")
      (node (ref "E30") (pin "9") (pinfunction "Q_9") (pintype "output"))
      (node (ref "E8") (pin "1") (pinfunction "I0_1") (pintype "input"))
    )
    (net (code "48") (name "AIOT0L") (class "Default")
      (node (ref "E33") (pin "1") (pinfunction "O0_1") (pintype "output"))
      (node (ref "E34") (pin "5") (pinfunction "I1_5") (pintype "input"))
    )
    (net (code "49") (name "AIOT1L") (class "Default")
      (node (ref "E30") (pin "10") (pinfunction "PRE_10") (pintype "input"))
      (node (ref "E33") (pin "2") (pinfunction "O1_2") (pintype "output"))
    )
    (net (code "50") (name "AIOT2H") (class "Default")
      (node (ref "E3") (pin "10") (pinfunction "O_10") (pintype "output"))
      (node (ref "E8") (pin "4") (pinfunction "I0_4") (pintype "input"))
    )
    (net (code "51") (name "AIOT2L") (class "Default")
      (node (ref "E3") (pin "11") (pinfunction "I_11") (pintype "input"))
      (node (ref "E33") (pin "3") (pinfunction "O2_3") (pintype "output"))
    )
    (net (code "52") (name "AIOT3H") (class "Default")
      (node (ref "E16") (pin "9") (pinfunction "I0_9") (pintype "input"))
      (node (ref "E3") (pin "6") (pinfunction "O_6") (pintype "output"))
    )
    (net (code "53") (name "AIOT3L") (class "Default")
      (node (ref "E3") (pin "5") (pinfunction "I_5") (pintype "input"))
      (node (ref "E33") (pin "4") (pinfunction "O3_4") (pintype "output"))
      (node (ref "E34") (pin "1") (pinfunction "I0_1") (pintype "input"))
    )
    (net (code "54") (name "AIOT4L") (class "Default")
      (node (ref "E33") (pin "5") (pinfunction "O4_5") (pintype "output"))
      (node (ref "E44") (pin "10") (pinfunction "B_10") (pintype "input"))
    )
    (net (code "55") (name "AIOT5L") (class "Default")
      (node (ref "E33") (pin "6") (pinfunction "O5_6") (pintype "output"))
      (node (ref "E43") (pin "1") (pinfunction "I0_1") (pintype "input"))
      (node (ref "E43") (pin "2") (pinfunction "I1_2") (pintype "input"))
      (node (ref "E43") (pin "4") (pinfunction "I0_4") (pintype "input"))
    )
    (net (code "56") (name "AIOT6L") (class "Default")
      (node (ref "E33") (pin "7") (pinfunction "O6_7") (pintype "output"))
      (node (ref "E35") (pin "10") (pinfunction "PRE_10") (pintype "input"))
    )
    (net (code "57") (name "AIOT7L") (class "Default")
      (node (ref "E13") (pin "5") (pinfunction "I1_5") (pintype "input"))
      (node (ref "E33") (pin "9") (pinfunction "O7_9") (pintype "output"))
    )
    (net (code "58") (name "AIOTL") (class "Default")
      (node (ref "E16") (pin "2") (pinfunction "I1_2") (pintype "input"))
      (node (ref "E2") (pin "8") (pinfunction "O_8") (pintype "output"))
      (node (ref "E33") (pin "12") (pinfunction "D_12") (pintype "input"))
    )
    (net (code "59") (name "AREADY") (class "Default")
      (node (ref "E12") (pin "11") (pinfunction "CLK_11") (pintype "input"))
      (node (ref "E13") (pin "11") (pinfunction "O_11") (pintype "output"))
    )
    (net (code "60") (name "AREADYH") (class "Default")
      (node (ref "E47") (pin "8") (pinfunction "CLAMP_8") (pintype "input"))
      (node (ref "J1") (pin "LL") (pinfunction "32_LL") (pintype "bidirectional"))
      (node (ref "R5") (pin "1") (pinfunction "1_1") (pintype "passive"))
      (node (ref "R6") (pin "1") (pinfunction "1_1") (pintype "passive"))
    )
    (net (code "61") (name "AREADYL") (class "Default")
      (node (ref "E4") (pin "10") (pinfunction "I1_10") (pintype "input"))
      (node (ref "E4") (pin "12") (pinfunction "I2_12") (pintype "input"))
      (node (ref "E4") (pin "13") (pinfunction "I3_13") (pintype "input"))
      (node (ref "E4") (pin "9") (pinfunction "I0_9") (pintype "input"))
      (node (ref "E47") (pin "11") (pinfunction "CLAMP_11") (pintype "input"))
      (node (ref "J1") (pin "FF") (pinfunction "28_FF") (pintype "bidirectional"))
      (node (ref "R10") (pin "1") (pinfunction "1_1") (pintype "passive"))
    )
    (net (code "62") (name "ASTROBEH") (class "Default")
      (node (ref "E42") (pin "11") (pinfunction "O_11") (pintype "output"))
      (node (ref "E47") (pin "9") (pinfunction "CLAMP_9") (pintype "input"))
      (node (ref "J1") (pin "JJ") (pinfunction "30_JJ") (pintype "bidirectional"))
    )
    (net (code "63") (name "ASTROBEL") (class "Default")
      (node (ref "E42") (pin "6") (pinfunction "O_6") (pintype "output"))
      (node (ref "E47") (pin "12") (pinfunction "CLAMP_12") (pintype "input"))
      (node (ref "J1") (pin "DD") (pinfunction "26_DD") (pintype "bidirectional"))
    )
    (net (code "64") (name "BCTLFLGH") (class "Default")
      (node (ref "E31") (pin "2") (pinfunction "I1_2") (pintype "input"))
      (node (ref "E35") (pin "5") (pinfunction "Q_5") (pintype "output"))
    )
    (net (code "65") (name "BD00") (class "Default")
      (node (ref "E5") (pin "11") (pinfunction "O1_11") (pintype "input"))
      (node (ref "E6") (pin "15") (pinfunction "Q4_15") (pintype "output"))
    )
    (net (code "66") (name "BD00H") (class "Default")
      (node (ref "E17") (pin "11") (pinfunction "CLAMP_11") (pintype "input"))
      (node (ref "E7") (pin "11") (pinfunction "O_11") (pintype "output"))
      (node (ref "J2") (pin "B") (pinfunction "2_B") (pintype "bidirectional"))
    )
    (net (code "67") (name "BD00L") (class "Default")
      (node (ref "E6") (pin "14") (pinfunction "~{Q4}_14") (pintype "output"))
      (node (ref "E7") (pin "12") (pinfunction "I0_12") (pintype "input"))
      (node (ref "E7") (pin "13") (pinfunction "I1_13") (pintype "input"))
    )
    (net (code "68") (name "BD01") (class "Default")
      (node (ref "E5") (pin "14") (pinfunction "O0_14") (pintype "input"))
      (node (ref "E6") (pin "10") (pinfunction "Q3_10") (pintype "output"))
    )
    (net (code "69") (name "BD01H") (class "Default")
      (node (ref "E17") (pin "12") (pinfunction "CLAMP_12") (pintype "input"))
      (node (ref "E7") (pin "8") (pinfunction "O_8") (pintype "output"))
      (node (ref "J2") (pin "D") (pinfunction "4_D") (pintype "bidirectional"))
    )
    (net (code "70") (name "BD01L") (class "Default")
      (node (ref "E6") (pin "11") (pinfunction "~{Q3}_11") (pintype "output"))
      (node (ref "E7") (pin "10") (pinfunction "I1_10") (pintype "input"))
      (node (ref "E7") (pin "9") (pinfunction "I0_9") (pintype "input"))
    )
    (net (code "71") (name "BD02") (class "Default")
      (node (ref "E5") (pin "5") (pinfunction "O3_5") (pintype "input"))
      (node (ref "E6") (pin "2") (pinfunction "Q1_2") (pintype "output"))
    )
    (net (code "72") (name "BD02H") (class "Default")
      (node (ref "E17") (pin "8") (pinfunction "CLAMP_8") (pintype "input"))
      (node (ref "E7") (pin "6") (pinfunction "O_6") (pintype "output"))
      (node (ref "J2") (pin "F") (pinfunction "6_F") (pintype "bidirectional"))
    )
    (net (code "73") (name "BD02L") (class "Default")
      (node (ref "E6") (pin "3") (pinfunction "~{Q1}_3") (pintype "output"))
      (node (ref "E7") (pin "4") (pinfunction "I0_4") (pintype "input"))
      (node (ref "E7") (pin "5") (pinfunction "I1_5") (pintype "input"))
    )
    (net (code "74") (name "BD03") (class "Default")
      (node (ref "E5") (pin "2") (pinfunction "O2_2") (pintype "input"))
      (node (ref "E6") (pin "7") (pinfunction "Q2_7") (pintype "output"))
    )
    (net (code "75") (name "BD03H") (class "Default")
      (node (ref "E17") (pin "9") (pinfunction "CLAMP_9") (pintype "input"))
      (node (ref "E7") (pin "3") (pinfunction "O_3") (pintype "output"))
      (node (ref "J2") (pin "J") (pinfunction "8_J") (pintype "bidirectional"))
    )
    (net (code "76") (name "BD03L") (class "Default")
      (node (ref "E6") (pin "6") (pinfunction "~{Q2}_6") (pintype "output"))
      (node (ref "E7") (pin "1") (pinfunction "I0_1") (pintype "input"))
      (node (ref "E7") (pin "2") (pinfunction "I1_2") (pintype "input"))
    )
    (net (code "77") (name "BD04") (class "Default")
      (node (ref "E19") (pin "11") (pinfunction "O1_11") (pintype "input"))
      (node (ref "E20") (pin "15") (pinfunction "Q4_15") (pintype "output"))
    )
    (net (code "78") (name "BD04H") (class "Default")
      (node (ref "E21") (pin "8") (pinfunction "O_8") (pintype "output"))
      (node (ref "E22") (pin "9") (pinfunction "CLAMP_9") (pintype "input"))
      (node (ref "J2") (pin "L") (pinfunction "10_L") (pintype "bidirectional"))
    )
    (net (code "79") (name "BD04L") (class "Default")
      (node (ref "E20") (pin "14") (pinfunction "~{Q4}_14") (pintype "output"))
      (node (ref "E21") (pin "10") (pinfunction "I1_10") (pintype "input"))
      (node (ref "E21") (pin "9") (pinfunction "I0_9") (pintype "input"))
    )
    (net (code "80") (name "BD05") (class "Default")
      (node (ref "E19") (pin "14") (pinfunction "O0_14") (pintype "input"))
      (node (ref "E20") (pin "10") (pinfunction "Q3_10") (pintype "output"))
    )
    (net (code "81") (name "BD05H") (class "Default")
      (node (ref "E21") (pin "11") (pinfunction "O_11") (pintype "output"))
      (node (ref "E22") (pin "8") (pinfunction "CLAMP_8") (pintype "input"))
      (node (ref "J2") (pin "N") (pinfunction "12_N") (pintype "bidirectional"))
    )
    (net (code "82") (name "BD05L") (class "Default")
      (node (ref "E20") (pin "11") (pinfunction "~{Q3}_11") (pintype "output"))
      (node (ref "E21") (pin "12") (pinfunction "I0_12") (pintype "input"))
      (node (ref "E21") (pin "13") (pinfunction "I1_13") (pintype "input"))
    )
    (net (code "83") (name "BD06") (class "Default")
      (node (ref "E19") (pin "5") (pinfunction "O3_5") (pintype "input"))
      (node (ref "E20") (pin "2") (pinfunction "Q1_2") (pintype "output"))
    )
    (net (code "84") (name "BD06H") (class "Default")
      (node (ref "E21") (pin "6") (pinfunction "O_6") (pintype "output"))
      (node (ref "E22") (pin "11") (pinfunction "CLAMP_11") (pintype "input"))
      (node (ref "J2") (pin "R") (pinfunction "14_R") (pintype "bidirectional"))
    )
    (net (code "85") (name "BD06L") (class "Default")
      (node (ref "E20") (pin "3") (pinfunction "~{Q1}_3") (pintype "output"))
      (node (ref "E21") (pin "4") (pinfunction "I0_4") (pintype "input"))
      (node (ref "E21") (pin "5") (pinfunction "I1_5") (pintype "input"))
    )
    (net (code "86") (name "BD07") (class "Default")
      (node (ref "E19") (pin "2") (pinfunction "O2_2") (pintype "input"))
      (node (ref "E20") (pin "7") (pinfunction "Q2_7") (pintype "output"))
    )
    (net (code "87") (name "BD07H") (class "Default")
      (node (ref "E21") (pin "3") (pinfunction "O_3") (pintype "output"))
      (node (ref "E22") (pin "12") (pinfunction "CLAMP_12") (pintype "input"))
      (node (ref "J2") (pin "T") (pinfunction "16_T") (pintype "bidirectional"))
    )
    (net (code "88") (name "BD07L") (class "Default")
      (node (ref "E20") (pin "6") (pinfunction "~{Q2}_6") (pintype "output"))
      (node (ref "E21") (pin "1") (pinfunction "I0_1") (pintype "input"))
      (node (ref "E21") (pin "2") (pinfunction "I1_2") (pintype "input"))
    )
    (net (code "89") (name "BD08") (class "Default")
      (node (ref "E36") (pin "11") (pinfunction "O1_11") (pintype "input"))
      (node (ref "E37") (pin "15") (pinfunction "Q4_15") (pintype "output"))
    )
    (net (code "90") (name "BD08H") (class "Default")
      (node (ref "E38") (pin "8") (pinfunction "O_8") (pintype "output"))
      (node (ref "E46") (pin "2") (pinfunction "CLAMP_2") (pintype "input"))
      (node (ref "J2") (pin "V") (pinfunction "18_V") (pintype "bidirectional"))
    )
    (net (code "91") (name "BD08L") (class "Default")
      (node (ref "E37") (pin "14") (pinfunction "~{Q4}_14") (pintype "output"))
      (node (ref "E38") (pin "10") (pinfunction "I1_10") (pintype "input"))
      (node (ref "E38") (pin "9") (pinfunction "I0_9") (pintype "input"))
    )
    (net (code "92") (name "BD09") (class "Default")
      (node (ref "E36") (pin "14") (pinfunction "O0_14") (pintype "input"))
      (node (ref "E37") (pin "10") (pinfunction "Q3_10") (pintype "output"))
    )
    (net (code "93") (name "BD09H") (class "Default")
      (node (ref "E38") (pin "11") (pinfunction "O_11") (pintype "output"))
      (node (ref "E46") (pin "3") (pinfunction "CLAMP_3") (pintype "input"))
      (node (ref "J2") (pin "X") (pinfunction "20_X") (pintype "bidirectional"))
    )
    (net (code "94") (name "BD09L") (class "Default")
      (node (ref "E37") (pin "11") (pinfunction "~{Q3}_11") (pintype "output"))
      (node (ref "E38") (pin "12") (pinfunction "I0_12") (pintype "input"))
      (node (ref "E38") (pin "13") (pinfunction "I1_13") (pintype "input"))
    )
    (net (code "95") (name "BD10") (class "Default")
      (node (ref "E36") (pin "5") (pinfunction "O3_5") (pintype "input"))
      (node (ref "E37") (pin "2") (pinfunction "Q1_2") (pintype "output"))
    )
    (net (code "96") (name "BD10H") (class "Default")
      (node (ref "E38") (pin "6") (pinfunction "O_6") (pintype "output"))
      (node (ref "E46") (pin "7") (pinfunction "CLAMP_7") (pintype "input"))
      (node (ref "J2") (pin "Z") (pinfunction "22_Z") (pintype "bidirectional"))
    )
    (net (code "97") (name "BD10L") (class "Default")
      (node (ref "E37") (pin "3") (pinfunction "~{Q1}_3") (pintype "output"))
      (node (ref "E38") (pin "4") (pinfunction "I0_4") (pintype "input"))
      (node (ref "E38") (pin "5") (pinfunction "I1_5") (pintype "input"))
    )
    (net (code "98") (name "BD11") (class "Default")
      (node (ref "E36") (pin "2") (pinfunction "O2_2") (pintype "input"))
      (node (ref "E37") (pin "7") (pinfunction "Q2_7") (pintype "output"))
    )
    (net (code "99") (name "BD11H") (class "Default")
      (node (ref "E38") (pin "3") (pinfunction "O_3") (pintype "output"))
      (node (ref "E46") (pin "5") (pinfunction "CLAMP_5") (pintype "input"))
      (node (ref "J2") (pin "BB") (pinfunction "24_BB") (pintype "bidirectional"))
    )
    (net (code "100") (name "BD11L") (class "Default")
      (node (ref "E37") (pin "6") (pinfunction "~{Q2}_6") (pintype "output"))
      (node (ref "E38") (pin "1") (pinfunction "I0_1") (pintype "input"))
      (node (ref "E38") (pin "2") (pinfunction "I1_2") (pintype "input"))
    )
    (net (code "101") (name "BDFLAG") (class "Default")
      (node (ref "E12") (pin "5") (pinfunction "Q_5") (pintype "output"))
      (node (ref "E16") (pin "4") (pinfunction "I0_4") (pintype "input"))
      (node (ref "E8") (pin "12") (pinfunction "I0_12") (pintype "input"))
    )
    (net (code "102") (name "BDONEH") (class "Default")
      (node (ref "E23") (pin "8") (pinfunction "O_8") (pintype "output"))
      (node (ref "E48") (pin "2") (pinfunction "CLAMP_2") (pintype "input"))
      (node (ref "J2") (pin "NN") (pinfunction "34_NN") (pintype "bidirectional"))
    )
    (net (code "103") (name "BDONEL") (class "Default")
      (node (ref "E23") (pin "6") (pinfunction "O_6") (pintype "output"))
      (node (ref "E23") (pin "9") (pinfunction "I0_9") (pintype "input"))
      (node (ref "E48") (pin "5") (pinfunction "CLAMP_5") (pintype "input"))
      (node (ref "J2") (pin "RR") (pinfunction "36_RR") (pintype "bidirectional"))
    )
    (net (code "104") (name "BFLAGH") (class "Default")
      (node (ref "E43") (pin "11") (pinfunction "O_11") (pintype "output"))
      (node (ref "E48") (pin "8") (pinfunction "CLAMP_8") (pintype "input"))
      (node (ref "J2") (pin "TT") (pinfunction "38_TT") (pintype "bidirectional"))
    )
    (net (code "105") (name "BINITH") (class "Default")
      (node (ref "E27") (pin "6") (pinfunction "O_6") (pintype "output"))
      (node (ref "E48") (pin "7") (pinfunction "CLAMP_7") (pintype "input"))
      (node (ref "J2") (pin "VV") (pinfunction "40_VV") (pintype "bidirectional"))
    )
    (net (code "106") (name "BINTENH") (class "Default")
      (node (ref "E16") (pin "5") (pinfunction "I1_5") (pintype "input"))
      (node (ref "E30") (pin "5") (pinfunction "Q_5") (pintype "output"))
    )
    (net (code "107") (name "BIOT0L") (class "Default")
      (node (ref "E29") (pin "1") (pinfunction "O0_1") (pintype "output"))
      (node (ref "E34") (pin "12") (pinfunction "I0_12") (pintype "input"))
    )
    (net (code "108") (name "BIOT1L") (class "Default")
      (node (ref "E29") (pin "2") (pinfunction "O1_2") (pintype "output"))
      (node (ref "E30") (pin "4") (pinfunction "PRE_4") (pintype "input"))
    )
    (net (code "109") (name "BIOT2H") (class "Default")
      (node (ref "E3") (pin "12") (pinfunction "O_12") (pintype "output"))
      (node (ref "E8") (pin "13") (pinfunction "I1_13") (pintype "input"))
    )
    (net (code "110") (name "BIOT2L") (class "Default")
      (node (ref "E29") (pin "3") (pinfunction "O2_3") (pintype "output"))
      (node (ref "E3") (pin "13") (pinfunction "I_13") (pintype "input"))
    )
    (net (code "111") (name "BIOT3H") (class "Default")
      (node (ref "E16") (pin "13") (pinfunction "I1_13") (pintype "input"))
      (node (ref "E3") (pin "4") (pinfunction "O_4") (pintype "output"))
    )
    (net (code "112") (name "BIOT3L") (class "Default")
      (node (ref "E29") (pin "4") (pinfunction "O3_4") (pintype "output"))
      (node (ref "E3") (pin "3") (pinfunction "I_3") (pintype "input"))
      (node (ref "E34") (pin "9") (pinfunction "I0_9") (pintype "input"))
    )
    (net (code "113") (name "BIOT4L") (class "Default")
      (node (ref "E29") (pin "5") (pinfunction "O4_5") (pintype "output"))
      (node (ref "E44") (pin "2") (pinfunction "B_2") (pintype "input"))
    )
    (net (code "114") (name "BIOT5L") (class "Default")
      (node (ref "E19") (pin "7") (pinfunction "D0_7") (pintype "input"))
      (node (ref "E19") (pin "9") (pinfunction "D1_9") (pintype "input"))
      (node (ref "E29") (pin "6") (pinfunction "O5_6") (pintype "output"))
      (node (ref "E36") (pin "7") (pinfunction "D0_7") (pintype "input"))
      (node (ref "E36") (pin "9") (pinfunction "D1_9") (pintype "input"))
      (node (ref "E43") (pin "5") (pinfunction "I1_5") (pintype "input"))
      (node (ref "E5") (pin "7") (pinfunction "D0_7") (pintype "input"))
      (node (ref "E5") (pin "9") (pinfunction "D1_9") (pintype "input"))
    )
    (net (code "115") (name "BIOT6L") (class "Default")
      (node (ref "E29") (pin "7") (pinfunction "O6_7") (pintype "output"))
      (node (ref "E35") (pin "4") (pinfunction "PRE_4") (pintype "input"))
    )
    (net (code "116") (name "BIOT7L") (class "Default")
      (node (ref "E13") (pin "1") (pinfunction "I0_1") (pintype "input"))
      (node (ref "E29") (pin "9") (pinfunction "O7_9") (pintype "output"))
    )
    (net (code "117") (name "BIOTL") (class "Default")
      (node (ref "E1") (pin "8") (pinfunction "O_8") (pintype "output"))
      (node (ref "E16") (pin "1") (pinfunction "I0_1") (pintype "input"))
      (node (ref "E29") (pin "12") (pinfunction "D_12") (pintype "input"))
    )
    (net (code "118") (name "BREADY") (class "Default")
      (node (ref "E12") (pin "3") (pinfunction "CLK_3") (pintype "input"))
      (node (ref "E13") (pin "8") (pinfunction "O_8") (pintype "output"))
    )
    (net (code "119") (name "BREADYH") (class "Default")
      (node (ref "E48") (pin "3") (pinfunction "CLAMP_3") (pintype "input"))
      (node (ref "J2") (pin "LL") (pinfunction "32_LL") (pintype "bidirectional"))
      (node (ref "R3") (pin "1") (pinfunction "1_1") (pintype "passive"))
      (node (ref "R4") (pin "1") (pinfunction "1_1") (pintype "passive"))
    )
    (net (code "120") (name "BREADYL") (class "Default")
      (node (ref "E18") (pin "10") (pinfunction "I1_10") (pintype "input"))
      (node (ref "E18") (pin "12") (pinfunction "I2_12") (pintype "input"))
      (node (ref "E18") (pin "13") (pinfunction "I3_13") (pintype "input"))
      (node (ref "E18") (pin "9") (pinfunction "I0_9") (pintype "input"))
      (node (ref "E48") (pin "12") (pinfunction "CLAMP_12") (pintype "input"))
      (node (ref "J2") (pin "FF") (pinfunction "28_FF") (pintype "bidirectional"))
      (node (ref "R9") (pin "1") (pinfunction "1_1") (pintype "passive"))
    )
    (net (code "121") (name "BSTROBEH") (class "Default")
      (node (ref "E42") (pin "3") (pinfunction "O_3") (pintype "output"))
      (node (ref "E48") (pin "11") (pinfunction "CLAMP_11") (pintype "input"))
      (node (ref "J2") (pin "JJ") (pinfunction "30_JJ") (pintype "bidirectional"))
    )
    (net (code "122") (name "BSTROBEL") (class "Default")
      (node (ref "E42") (pin "8") (pinfunction "O_8") (pintype "output"))
      (node (ref "E48") (pin "9") (pinfunction "CLAMP_9") (pintype "input"))
      (node (ref "J2") (pin "DD") (pinfunction "26_DD") (pintype "bidirectional"))
    )
    (net (code "123") (name "DATA0") (class "Default")
      (node (ref "E10") (pin "4") (pinfunction "D1_4") (pintype "input"))
      (node (ref "E5") (pin "10") (pinfunction "I1_10") (pintype "output"))
      (node (ref "E6") (pin "13") (pinfunction "D4_13") (pintype "input"))
    )
    (net (code "124") (name "DATA1") (class "Default")
      (node (ref "E10") (pin "5") (pinfunction "D2_5") (pintype "input"))
      (node (ref "E5") (pin "13") (pinfunction "I0_13") (pintype "output"))
      (node (ref "E6") (pin "12") (pinfunction "D3_12") (pintype "input"))
    )
    (net (code "125") (name "DATA2") (class "Default")
      (node (ref "E10") (pin "13") (pinfunction "D4_13") (pintype "input"))
      (node (ref "E5") (pin "6") (pinfunction "I3_6") (pintype "output"))
      (node (ref "E6") (pin "4") (pinfunction "D1_4") (pintype "input"))
    )
    (net (code "126") (name "DATA3") (class "Default")
      (node (ref "E10") (pin "12") (pinfunction "D3_12") (pintype "input"))
      (node (ref "E5") (pin "3") (pinfunction "I2_3") (pintype "output"))
      (node (ref "E6") (pin "5") (pinfunction "D2_5") (pintype "input"))
    )
    (net (code "127") (name "DATA4") (class "Default")
      (node (ref "E19") (pin "10") (pinfunction "I1_10") (pintype "output"))
      (node (ref "E20") (pin "13") (pinfunction "D4_13") (pintype "input"))
      (node (ref "E25") (pin "4") (pinfunction "D1_4") (pintype "input"))
    )
    (net (code "128") (name "DATA5") (class "Default")
      (node (ref "E19") (pin "13") (pinfunction "I0_13") (pintype "output"))
      (node (ref "E20") (pin "12") (pinfunction "D3_12") (pintype "input"))
      (node (ref "E25") (pin "5") (pinfunction "D2_5") (pintype "input"))
    )
    (net (code "129") (name "DATA6") (class "Default")
      (node (ref "E19") (pin "6") (pinfunction "I3_6") (pintype "output"))
      (node (ref "E20") (pin "4") (pinfunction "D1_4") (pintype "input"))
      (node (ref "E25") (pin "13") (pinfunction "D4_13") (pintype "input"))
    )
    (net (code "130") (name "DATA7") (class "Default")
      (node (ref "E19") (pin "3") (pinfunction "I2_3") (pintype "output"))
      (node (ref "E20") (pin "5") (pinfunction "D2_5") (pintype "input"))
      (node (ref "E25") (pin "12") (pinfunction "D3_12") (pintype "input"))
    )
    (net (code "131") (name "DATA8") (class "Default")
      (node (ref "E36") (pin "10") (pinfunction "I1_10") (pintype "output"))
      (node (ref "E37") (pin "13") (pinfunction "D4_13") (pintype "input"))
      (node (ref "E40") (pin "4") (pinfunction "D1_4") (pintype "input"))
    )
    (net (code "132") (name "DATA9") (class "Default")
      (node (ref "E36") (pin "13") (pinfunction "I0_13") (pintype "output"))
      (node (ref "E37") (pin "12") (pinfunction "D3_12") (pintype "input"))
      (node (ref "E40") (pin "5") (pinfunction "D2_5") (pintype "input"))
    )
    (net (code "133") (name "DATA10") (class "Default")
      (node (ref "E36") (pin "6") (pinfunction "I3_6") (pintype "output"))
      (node (ref "E37") (pin "4") (pinfunction "D1_4") (pintype "input"))
      (node (ref "E40") (pin "13") (pinfunction "D4_13") (pintype "input"))
    )
    (net (code "134") (name "DATA11") (class "Default")
      (node (ref "E36") (pin "3") (pinfunction "I2_3") (pintype "output"))
      (node (ref "E37") (pin "5") (pinfunction "D2_5") (pintype "input"))
      (node (ref "E40") (pin "12") (pinfunction "D3_12") (pintype "input"))
    )
    (net (code "135") (name "GND") (class "Default")
      (node (ref "C1") (pin "2") (pinfunction "2_2") (pintype "passive"))
      (node (ref "C10") (pin "2") (pinfunction "2_2") (pintype "passive"))
      (node (ref "C100") (pin "-") (pinfunction "-_-") (pintype "passive"))
      (node (ref "C101") (pin "-") (pinfunction "-_-") (pintype "passive"))
      (node (ref "C102") (pin "-") (pinfunction "-_-") (pintype "passive"))
      (node (ref "C11") (pin "2") (pinfunction "2_2") (pintype "passive"))
      (node (ref "C12") (pin "2") (pinfunction "2_2") (pintype "passive"))
      (node (ref "C13") (pin "2") (pinfunction "2_2") (pintype "passive"))
      (node (ref "C14") (pin "2") (pinfunction "2_2") (pintype "passive"))
      (node (ref "C15") (pin "2") (pinfunction "2_2") (pintype "passive"))
      (node (ref "C16") (pin "2") (pinfunction "2_2") (pintype "passive"))
      (node (ref "C17") (pin "2") (pinfunction "2_2") (pintype "passive"))
      (node (ref "C18") (pin "2") (pinfunction "2_2") (pintype "passive"))
      (node (ref "C19") (pin "2") (pinfunction "2_2") (pintype "passive"))
      (node (ref "C2") (pin "2") (pinfunction "2_2") (pintype "passive"))
      (node (ref "C20") (pin "2") (pinfunction "2_2") (pintype "passive"))
      (node (ref "C21") (pin "2") (pinfunction "2_2") (pintype "passive"))
      (node (ref "C22") (pin "2") (pinfunction "2_2") (pintype "passive"))
      (node (ref "C23") (pin "2") (pinfunction "2_2") (pintype "passive"))
      (node (ref "C24") (pin "2") (pinfunction "2_2") (pintype "passive"))
      (node (ref "C25") (pin "2") (pinfunction "2_2") (pintype "passive"))
      (node (ref "C26") (pin "2") (pinfunction "2_2") (pintype "passive"))
      (node (ref "C27") (pin "2") (pinfunction "2_2") (pintype "passive"))
      (node (ref "C28") (pin "2") (pinfunction "2_2") (pintype "passive"))
      (node (ref "C29") (pin "2") (pinfunction "2_2") (pintype "passive"))
      (node (ref "C3") (pin "2") (pinfunction "2_2") (pintype "passive"))
      (node (ref "C30") (pin "2") (pinfunction "2_2") (pintype "passive"))
      (node (ref "C31") (pin "2") (pinfunction "2_2") (pintype "passive"))
      (node (ref "C32") (pin "2") (pinfunction "2_2") (pintype "passive"))
      (node (ref "C33") (pin "2") (pinfunction "2_2") (pintype "passive"))
      (node (ref "C34") (pin "2") (pinfunction "2_2") (pintype "passive"))
      (node (ref "C4") (pin "2") (pinfunction "2_2") (pintype "passive"))
      (node (ref "C5") (pin "2") (pinfunction "2_2") (pintype "passive"))
      (node (ref "C6") (pin "2") (pinfunction "2_2") (pintype "passive"))
      (node (ref "C7") (pin "2") (pinfunction "2_2") (pintype "passive"))
      (node (ref "C8") (pin "2") (pinfunction "2_2") (pintype "passive"))
      (node (ref "C9") (pin "2") (pinfunction "2_2") (pintype "passive"))
      (node (ref "E14") (pin "7") (pinfunction "FORCE0_7") (pintype "input"))
      (node (ref "E14") (pin "9") (pinfunction "FORCE0_9") (pintype "input"))
      (node (ref "E32") (pin "7") (pinfunction "FORCE0_7") (pintype "input"))
      (node (ref "E32") (pin "9") (pinfunction "FORCE0_9") (pintype "input"))
      (node (ref "E44") (pin "1") (pinfunction "A_1") (pintype "input"))
      (node (ref "E44") (pin "9") (pinfunction "A_9") (pintype "input"))
      (node (ref "J1") (pin "A") (pinfunction "1_A") (pintype "bidirectional"))
      (node (ref "J1") (pin "AA") (pinfunction "23_AA") (pintype "bidirectional"))
      (node (ref "J1") (pin "C") (pinfunction "3_C") (pintype "bidirectional"))
      (node (ref "J1") (pin "CC") (pinfunction "25_CC") (pintype "bidirectional"))
      (node (ref "J1") (pin "E") (pinfunction "5_E") (pintype "bidirectional"))
      (node (ref "J1") (pin "EE") (pinfunction "27_EE") (pintype "bidirectional"))
      (node (ref "J1") (pin "H") (pinfunction "7_H") (pintype "bidirectional"))
      (node (ref "J1") (pin "HH") (pinfunction "29_HH") (pintype "bidirectional"))
      (node (ref "J1") (pin "K") (pinfunction "9_K") (pintype "bidirectional"))
      (node (ref "J1") (pin "KK") (pinfunction "31_KK") (pintype "bidirectional"))
      (node (ref "J1") (pin "M") (pinfunction "11_M") (pintype "bidirectional"))
      (node (ref "J1") (pin "MM") (pinfunction "33_MM") (pintype "bidirectional"))
      (node (ref "J1") (pin "P") (pinfunction "13_P") (pintype "bidirectional"))
      (node (ref "J1") (pin "PP") (pinfunction "35_PP") (pintype "bidirectional"))
      (node (ref "J1") (pin "S") (pinfunction "15_S") (pintype "bidirectional"))
      (node (ref "J1") (pin "SS") (pinfunction "37_SS") (pintype "bidirectional"))
      (node (ref "J1") (pin "U") (pinfunction "17_U") (pintype "bidirectional"))
      (node (ref "J1") (pin "UU") (pinfunction "39_UU") (pintype "bidirectional"))
      (node (ref "J1") (pin "W") (pinfunction "19_W") (pintype "bidirectional"))
      (node (ref "J1") (pin "Y") (pinfunction "21_Y") (pintype "bidirectional"))
      (node (ref "J2") (pin "A") (pinfunction "1_A") (pintype "bidirectional"))
      (node (ref "J2") (pin "AA") (pinfunction "23_AA") (pintype "bidirectional"))
      (node (ref "J2") (pin "C") (pinfunction "3_C") (pintype "bidirectional"))
      (node (ref "J2") (pin "CC") (pinfunction "25_CC") (pintype "bidirectional"))
      (node (ref "J2") (pin "E") (pinfunction "5_E") (pintype "bidirectional"))
      (node (ref "J2") (pin "EE") (pinfunction "27_EE") (pintype "bidirectional"))
      (node (ref "J2") (pin "H") (pinfunction "7_H") (pintype "bidirectional"))
      (node (ref "J2") (pin "HH") (pinfunction "29_HH") (pintype "bidirectional"))
      (node (ref "J2") (pin "K") (pinfunction "9_K") (pintype "bidirectional"))
      (node (ref "J2") (pin "KK") (pinfunction "31_KK") (pintype "bidirectional"))
      (node (ref "J2") (pin "M") (pinfunction "11_M") (pintype "bidirectional"))
      (node (ref "J2") (pin "MM") (pinfunction "33_MM") (pintype "bidirectional"))
      (node (ref "J2") (pin "P") (pinfunction "13_P") (pintype "bidirectional"))
      (node (ref "J2") (pin "PP") (pinfunction "35_PP") (pintype "bidirectional"))
      (node (ref "J2") (pin "S") (pinfunction "15_S") (pintype "bidirectional"))
      (node (ref "J2") (pin "SS") (pinfunction "37_SS") (pintype "bidirectional"))
      (node (ref "J2") (pin "U") (pinfunction "17_U") (pintype "bidirectional"))
      (node (ref "J2") (pin "UU") (pinfunction "39_UU") (pintype "bidirectional"))
      (node (ref "J2") (pin "W") (pinfunction "19_W") (pintype "bidirectional"))
      (node (ref "J2") (pin "Y") (pinfunction "21_Y") (pintype "bidirectional"))
      (node (ref "R14") (pin "1") (pinfunction "1_1") (pintype "passive"))
      (node (ref "R16") (pin "1") (pinfunction "1_1") (pintype "passive"))
      (node (ref "R18") (pin "1") (pinfunction "1_1") (pintype "passive"))
      (node (ref "R2") (pin "2") (pinfunction "2_2") (pintype "passive"))
      (node (ref "R20") (pin "1") (pinfunction "1_1") (pintype "passive"))
      (node (ref "U$2") (pin "AC1") (pinfunction "1_AC1") (pintype "bidirectional"))
      (node (ref "U$2") (pin "AC2") (pinfunction "1_AC2") (pintype "bidirectional"))
      (node (ref "U$2") (pin "AF1") (pinfunction "1_AF1") (pintype "bidirectional"))
      (node (ref "U$2") (pin "AF2") (pinfunction "1_AF2") (pintype "bidirectional"))
      (node (ref "U$2") (pin "AN1") (pinfunction "1_AN1") (pintype "bidirectional"))
      (node (ref "U$2") (pin "AN2") (pinfunction "1_AN2") (pintype "bidirectional"))
      (node (ref "U$2") (pin "AT1") (pinfunction "1_AT1") (pintype "bidirectional"))
      (node (ref "U$2") (pin "AT2") (pinfunction "1_AT2") (pintype "bidirectional"))
      (node (ref "U$2") (pin "BC1") (pinfunction "1_BC1") (pintype "bidirectional"))
      (node (ref "U$2") (pin "BC2") (pinfunction "1_BC2") (pintype "bidirectional"))
      (node (ref "U$2") (pin "BF1") (pinfunction "1_BF1") (pintype "bidirectional"))
      (node (ref "U$2") (pin "BF2") (pinfunction "1_BF2") (pintype "bidirectional"))
      (node (ref "U$2") (pin "BN1") (pinfunction "1_BN1") (pintype "bidirectional"))
      (node (ref "U$2") (pin "BN2") (pinfunction "1_BN2") (pintype "bidirectional"))
      (node (ref "U$2") (pin "BT1") (pinfunction "1_BT1") (pintype "bidirectional"))
      (node (ref "U$2") (pin "BT2") (pinfunction "1_BT2") (pintype "bidirectional"))
      (node (ref "U$2") (pin "CC1") (pinfunction "1_CC1") (pintype "bidirectional"))
      (node (ref "U$2") (pin "CC2") (pinfunction "1_CC2") (pintype "bidirectional"))
      (node (ref "U$2") (pin "CF1") (pinfunction "1_CF1") (pintype "bidirectional"))
      (node (ref "U$2") (pin "CF2") (pinfunction "1_CF2") (pintype "bidirectional"))
      (node (ref "U$2") (pin "CN1") (pinfunction "1_CN1") (pintype "bidirectional"))
      (node (ref "U$2") (pin "CN2") (pinfunction "1_CN2") (pintype "bidirectional"))
      (node (ref "U$2") (pin "CT1") (pinfunction "1_CT1") (pintype "bidirectional"))
      (node (ref "U$2") (pin "CT2") (pinfunction "1_CT2") (pintype "bidirectional"))
      (node (ref "U$2") (pin "DC1") (pinfunction "1_DC1") (pintype "bidirectional"))
      (node (ref "U$2") (pin "DC2") (pinfunction "1_DC2") (pintype "bidirectional"))
      (node (ref "U$2") (pin "DF1") (pinfunction "1_DF1") (pintype "bidirectional"))
      (node (ref "U$2") (pin "DF2") (pinfunction "1_DF2") (pintype "bidirectional"))
      (node (ref "U$2") (pin "DN1") (pinfunction "1_DN1") (pintype "bidirectional"))
      (node (ref "U$2") (pin "DN2") (pinfunction "1_DN2") (pintype "bidirectional"))
      (node (ref "U$2") (pin "DT1") (pinfunction "1_DT1") (pintype "bidirectional"))
      (node (ref "U$2") (pin "DT2") (pinfunction "1_DT2") (pintype "bidirectional"))
      (node (ref "W29") (pin "1") (pinfunction "1_1") (pintype "passive"))
      (node (ref "W30") (pin "1") (pinfunction "1_1") (pintype "passive"))
      (node (ref "W31") (pin "1") (pinfunction "1_1") (pintype "passive"))
      (node (ref "W32") (pin "1") (pinfunction "1_1") (pintype "passive"))
    )
    (net (code "136") (name "INITIALIZE") (class "Default")
      (node (ref "E32") (pin "3") (pinfunction "Y2_3") (pintype "input"))
      (node (ref "U$2") (pin "CR1") (pinfunction "1_CR1") (pintype "bidirectional"))
    )
    (net (code "137") (name "INITIALIZEH") (class "Default")
      (node (ref "E27") (pin "1") (pinfunction "I0_1") (pintype "input"))
      (node (ref "E27") (pin "2") (pinfunction "I1_2") (pintype "input"))
      (node (ref "E45") (pin "4") (pinfunction "O_4") (pintype "open_collector"))
      (node (ref "R1") (pin "1") (pinfunction "1_1") (pintype "passive"))
      (node (ref "R2") (pin "1") (pinfunction "1_1") (pintype "passive"))
    )
    (net (code "138") (name "INITIALIZEL") (class "Default")
      (node (ref "E32") (pin "4") (pinfunction "A2_4") (pintype "output"))
      (node (ref "E34") (pin "10") (pinfunction "I1_10") (pintype "input"))
      (node (ref "E34") (pin "13") (pinfunction "I1_13") (pintype "input"))
      (node (ref "E34") (pin "2") (pinfunction "I1_2") (pintype "input"))
      (node (ref "E34") (pin "4") (pinfunction "I0_4") (pintype "input"))
      (node (ref "E45") (pin "5") (pinfunction "I0_5") (pintype "input"))
      (node (ref "E45") (pin "6") (pinfunction "I1_6") (pintype "input"))
    )
    (net (code "139") (name "INITL") (class "Default")
      (node (ref "E10") (pin "1") (pinfunction "CLR_1") (pintype "input"))
      (node (ref "E13") (pin "2") (pinfunction "I1_2") (pintype "input"))
      (node (ref "E13") (pin "4") (pinfunction "I0_4") (pintype "input"))
      (node (ref "E20") (pin "1") (pinfunction "CLR_1") (pintype "input"))
      (node (ref "E25") (pin "1") (pinfunction "CLR_1") (pintype "input"))
      (node (ref "E27") (pin "12") (pinfunction "I0_12") (pintype "input"))
      (node (ref "E27") (pin "13") (pinfunction "I1_13") (pintype "input"))
      (node (ref "E27") (pin "3") (pinfunction "O_3") (pintype "output"))
      (node (ref "E27") (pin "4") (pinfunction "I0_4") (pintype "input"))
      (node (ref "E27") (pin "5") (pinfunction "I1_5") (pintype "input"))
      (node (ref "E37") (pin "1") (pinfunction "CLR_1") (pintype "input"))
      (node (ref "E40") (pin "1") (pinfunction "CLR_1") (pintype "input"))
      (node (ref "E6") (pin "1") (pinfunction "CLR_1") (pintype "input"))
    )
    (net (code "140") (name "IO_PAUSEH") (class "Default")
      (node (ref "E1") (pin "5") (pinfunction "I4_5") (pintype "input"))
      (node (ref "E1") (pin "6") (pinfunction "I5_6") (pintype "input"))
      (node (ref "E14") (pin "2") (pinfunction "A1_2") (pintype "output"))
      (node (ref "E2") (pin "5") (pinfunction "I4_5") (pintype "input"))
      (node (ref "E2") (pin "6") (pinfunction "I5_6") (pintype "input"))
    )
    (net (code "141") (name "MD03H") (class "Default")
      (node (ref "E14") (pin "10") (pinfunction "A1_10") (pintype "output"))
      (node (ref "E15") (pin "13") (pinfunction "I_13") (pintype "input"))
      (node (ref "W1") (pin "1") (pinfunction "1_1") (pintype "passive"))
      (node (ref "W13") (pin "1") (pinfunction "1_1") (pintype "passive"))
    )
    (net (code "142") (name "MD03L") (class "Default")
      (node (ref "E15") (pin "12") (pinfunction "O_12") (pintype "output"))
      (node (ref "W14") (pin "1") (pinfunction "1_1") (pintype "passive"))
      (node (ref "W2") (pin "1") (pinfunction "1_1") (pintype "passive"))
    )
    (net (code "143") (name "MD04H") (class "Default")
      (node (ref "E14") (pin "6") (pinfunction "A3_6") (pintype "output"))
      (node (ref "E15") (pin "1") (pinfunction "I_1") (pintype "input"))
      (node (ref "W15") (pin "1") (pinfunction "1_1") (pintype "passive"))
      (node (ref "W3") (pin "1") (pinfunction "1_1") (pintype "passive"))
    )
    (net (code "144") (name "MD04L") (class "Default")
      (node (ref "E15") (pin "2") (pinfunction "O_2") (pintype "output"))
      (node (ref "W16") (pin "1") (pinfunction "1_1") (pintype "passive"))
      (node (ref "W4") (pin "1") (pinfunction "1_1") (pintype "passive"))
    )
    (net (code "145") (name "MD05H") (class "Default")
      (node (ref "E14") (pin "4") (pinfunction "A2_4") (pintype "output"))
      (node (ref "E15") (pin "3") (pinfunction "I_3") (pintype "input"))
      (node (ref "W17") (pin "1") (pinfunction "1_1") (pintype "passive"))
      (node (ref "W5") (pin "1") (pinfunction "1_1") (pintype "passive"))
    )
    (net (code "146") (name "MD05L") (class "Default")
      (node (ref "E15") (pin "4") (pinfunction "O_4") (pintype "output"))
      (node (ref "W18") (pin "1") (pinfunction "1_1") (pintype "passive"))
      (node (ref "W6") (pin "1") (pinfunction "1_1") (pintype "passive"))
    )
    (net (code "147") (name "MD06H") (class "Default")
      (node (ref "E14") (pin "12") (pinfunction "A2_12") (pintype "output"))
      (node (ref "E15") (pin "11") (pinfunction "I_11") (pintype "input"))
      (node (ref "W19") (pin "1") (pinfunction "1_1") (pintype "passive"))
      (node (ref "W7") (pin "1") (pinfunction "1_1") (pintype "passive"))
    )
    (net (code "148") (name "MD06L") (class "Default")
      (node (ref "E15") (pin "10") (pinfunction "O_10") (pintype "output"))
      (node (ref "W20") (pin "1") (pinfunction "1_1") (pintype "passive"))
      (node (ref "W8") (pin "1") (pinfunction "1_1") (pintype "passive"))
    )
    (net (code "149") (name "MD07H") (class "Default")
      (node (ref "E14") (pin "14") (pinfunction "A3_14") (pintype "output"))
      (node (ref "E15") (pin "9") (pinfunction "I_9") (pintype "input"))
      (node (ref "W21") (pin "1") (pinfunction "1_1") (pintype "passive"))
      (node (ref "W9") (pin "1") (pinfunction "1_1") (pintype "passive"))
    )
    (net (code "150") (name "MD07L") (class "Default")
      (node (ref "E15") (pin "8") (pinfunction "O_8") (pintype "output"))
      (node (ref "W10") (pin "1") (pinfunction "1_1") (pintype "passive"))
      (node (ref "W22") (pin "1") (pinfunction "1_1") (pintype "passive"))
    )
    (net (code "151") (name "MD08H") (class "Default")
      (node (ref "E15") (pin "5") (pinfunction "I_5") (pintype "input"))
      (node (ref "E32") (pin "2") (pinfunction "A1_2") (pintype "output"))
      (node (ref "W11") (pin "1") (pinfunction "1_1") (pintype "passive"))
      (node (ref "W23") (pin "1") (pinfunction "1_1") (pintype "passive"))
    )
    (net (code "152") (name "MD08L") (class "Default")
      (node (ref "E15") (pin "6") (pinfunction "O_6") (pintype "output"))
      (node (ref "W12") (pin "1") (pinfunction "1_1") (pintype "passive"))
      (node (ref "W24") (pin "1") (pinfunction "1_1") (pintype "passive"))
    )
    (net (code "153") (name "MD09H") (class "Default")
      (node (ref "E29") (pin "13") (pinfunction "C_13") (pintype "input"))
      (node (ref "E32") (pin "14") (pinfunction "A3_14") (pintype "output"))
      (node (ref "E33") (pin "13") (pinfunction "C_13") (pintype "input"))
    )
    (net (code "154") (name "MD10H") (class "Default")
      (node (ref "E29") (pin "14") (pinfunction "B_14") (pintype "input"))
      (node (ref "E32") (pin "12") (pinfunction "A2_12") (pintype "output"))
      (node (ref "E33") (pin "14") (pinfunction "B_14") (pintype "input"))
    )
    (net (code "155") (name "MD11H") (class "Default")
      (node (ref "E29") (pin "15") (pinfunction "A_15") (pintype "input"))
      (node (ref "E32") (pin "10") (pinfunction "A1_10") (pintype "output"))
      (node (ref "E33") (pin "15") (pinfunction "A_15") (pintype "input"))
    )
    (net (code "156") (name "NC") (class "Default")
      (node (ref "E30") (pin "12") (pinfunction "D_12") (pintype "input"))
      (node (ref "E30") (pin "2") (pinfunction "D_2") (pintype "input"))
      (node (ref "E35") (pin "12") (pinfunction "D_12") (pintype "input"))
      (node (ref "E35") (pin "2") (pinfunction "D_2") (pintype "input"))
    )
    (net (code "157") (name "Net-(E1A-I0)") (class "Default")
      (node (ref "E1") (pin "1") (pinfunction "I0_1") (pintype "input"))
      (node (ref "W13") (pin "2") (pinfunction "2_2") (pintype "passive"))
      (node (ref "W14") (pin "2") (pinfunction "2_2") (pintype "passive"))
    )
    (net (code "158") (name "Net-(E1A-I1)") (class "Default")
      (node (ref "E1") (pin "2") (pinfunction "I1_2") (pintype "input"))
      (node (ref "W19") (pin "2") (pinfunction "2_2") (pintype "passive"))
      (node (ref "W20") (pin "2") (pinfunction "2_2") (pintype "passive"))
    )
    (net (code "159") (name "Net-(E1A-I2)") (class "Default")
      (node (ref "E1") (pin "3") (pinfunction "I2_3") (pintype "input"))
      (node (ref "W17") (pin "2") (pinfunction "2_2") (pintype "passive"))
      (node (ref "W18") (pin "2") (pinfunction "2_2") (pintype "passive"))
    )
    (net (code "160") (name "Net-(E1A-I3)") (class "Default")
      (node (ref "E1") (pin "4") (pinfunction "I3_4") (pintype "input"))
      (node (ref "W15") (pin "2") (pinfunction "2_2") (pintype "passive"))
      (node (ref "W16") (pin "2") (pinfunction "2_2") (pintype "passive"))
    )
    (net (code "161") (name "Net-(E1A-I6)") (class "Default")
      (node (ref "E1") (pin "11") (pinfunction "I6_11") (pintype "input"))
      (node (ref "W23") (pin "2") (pinfunction "2_2") (pintype "passive"))
      (node (ref "W24") (pin "2") (pinfunction "2_2") (pintype "passive"))
    )
    (net (code "162") (name "Net-(E1A-I7)") (class "Default")
      (node (ref "E1") (pin "12") (pinfunction "I7_12") (pintype "input"))
      (node (ref "W21") (pin "2") (pinfunction "2_2") (pintype "passive"))
      (node (ref "W22") (pin "2") (pinfunction "2_2") (pintype "passive"))
    )
    (net (code "163") (name "Net-(E2A-I0)") (class "Default")
      (node (ref "E2") (pin "1") (pinfunction "I0_1") (pintype "input"))
      (node (ref "W5") (pin "2") (pinfunction "2_2") (pintype "passive"))
      (node (ref "W6") (pin "2") (pinfunction "2_2") (pintype "passive"))
    )
    (net (code "164") (name "Net-(E2A-I1)") (class "Default")
      (node (ref "E2") (pin "2") (pinfunction "I1_2") (pintype "input"))
      (node (ref "W1") (pin "2") (pinfunction "2_2") (pintype "passive"))
      (node (ref "W2") (pin "2") (pinfunction "2_2") (pintype "passive"))
    )
    (net (code "165") (name "Net-(E2A-I2)") (class "Default")
      (node (ref "E2") (pin "3") (pinfunction "I2_3") (pintype "input"))
      (node (ref "W7") (pin "2") (pinfunction "2_2") (pintype "passive"))
      (node (ref "W8") (pin "2") (pinfunction "2_2") (pintype "passive"))
    )
    (net (code "166") (name "Net-(E2A-I3)") (class "Default")
      (node (ref "E2") (pin "4") (pinfunction "I3_4") (pintype "input"))
      (node (ref "W3") (pin "2") (pinfunction "2_2") (pintype "passive"))
      (node (ref "W4") (pin "2") (pinfunction "2_2") (pintype "passive"))
    )
    (net (code "167") (name "Net-(E2A-I6)") (class "Default")
      (node (ref "E2") (pin "11") (pinfunction "I6_11") (pintype "input"))
      (node (ref "W10") (pin "2") (pinfunction "2_2") (pintype "passive"))
      (node (ref "W9") (pin "2") (pinfunction "2_2") (pintype "passive"))
    )
    (net (code "168") (name "Net-(E2A-I7)") (class "Default")
      (node (ref "E2") (pin "12") (pinfunction "I7_12") (pintype "input"))
      (node (ref "W11") (pin "2") (pinfunction "2_2") (pintype "passive"))
      (node (ref "W12") (pin "2") (pinfunction "2_2") (pintype "passive"))
    )
    (net (code "169") (name "Net-(E3D-I)") (class "Default")
      (node (ref "E3") (pin "9") (pinfunction "I_9") (pintype "input"))
      (node (ref "E4") (pin "6") (pinfunction "O_6") (pintype "output"))
    )
    (net (code "170") (name "Net-(E4A-I0)") (class "Default")
      (node (ref "C34") (pin "1") (pinfunction "1_1") (pintype "passive"))
      (node (ref "E4") (pin "1") (pinfunction "I0_1") (pintype "input"))
      (node (ref "E4") (pin "2") (pinfunction "I1_2") (pintype "input"))
      (node (ref "E4") (pin "4") (pinfunction "I2_4") (pintype "input"))
      (node (ref "E4") (pin "5") (pinfunction "I3_5") (pintype "input"))
      (node (ref "R6") (pin "2") (pinfunction "2_2") (pintype "passive"))
    )
    (net (code "171") (name "Net-(E8B-O)") (class "Default")
      (node (ref "E8") (pin "6") (pinfunction "O_6") (pintype "output"))
      (node (ref "E8") (pin "9") (pinfunction "I0_9") (pintype "input"))
    )
    (net (code "172") (name "Net-(E8C-I1)") (class "Default")
      (node (ref "E8") (pin "10") (pinfunction "I1_10") (pintype "input"))
      (node (ref "E8") (pin "11") (pinfunction "O_11") (pintype "output"))
    )
    (net (code "173") (name "Net-(E10A-CLK)") (class "Default")
      (node (ref "E10") (pin "9") (pinfunction "CLK_9") (pintype "input"))
      (node (ref "E16") (pin "8") (pinfunction "O_8") (pintype "output"))
      (node (ref "E25") (pin "9") (pinfunction "CLK_9") (pintype "input"))
      (node (ref "E40") (pin "9") (pinfunction "CLK_9") (pintype "input"))
    )
    (net (code "174") (name "Net-(E12A-CLR)") (class "Default")
      (node (ref "E12") (pin "1") (pinfunction "CLR_1") (pintype "input"))
      (node (ref "E23") (pin "5") (pinfunction "I1_5") (pintype "input"))
      (node (ref "E34") (pin "8") (pinfunction "O_8") (pintype "output"))
    )
    (net (code "175") (name "Net-(E12A-~{Q})") (class "Default")
      (node (ref "E12") (pin "6") (pinfunction "~{Q}_6") (pintype "output"))
      (node (ref "E23") (pin "4") (pinfunction "I0_4") (pintype "input"))
    )
    (net (code "176") (name "Net-(E12B-CLR)") (class "Default")
      (node (ref "E12") (pin "13") (pinfunction "CLR_13") (pintype "input"))
      (node (ref "E23") (pin "13") (pinfunction "I1_13") (pintype "input"))
      (node (ref "E34") (pin "3") (pinfunction "O_3") (pintype "output"))
    )
    (net (code "177") (name "Net-(E12B-~{Q})") (class "Default")
      (node (ref "E12") (pin "8") (pinfunction "~{Q}_8") (pintype "output"))
      (node (ref "E23") (pin "12") (pinfunction "I0_12") (pintype "input"))
    )
    (net (code "178") (name "Net-(E13A-O)") (class "Default")
      (node (ref "E13") (pin "3") (pinfunction "O_3") (pintype "output"))
      (node (ref "E35") (pin "1") (pinfunction "CLR_1") (pintype "input"))
    )
    (net (code "179") (name "Net-(E13B-O)") (class "Default")
      (node (ref "E13") (pin "6") (pinfunction "O_6") (pintype "output"))
      (node (ref "E35") (pin "13") (pinfunction "CLR_13") (pintype "input"))
    )
    (net (code "180") (name "Net-(E13C-I0)") (class "Default")
      (node (ref "E13") (pin "9") (pinfunction "I0_9") (pintype "input"))
      (node (ref "E31") (pin "8") (pinfunction "O_8") (pintype "output"))
    )
    (net (code "181") (name "Net-(E13C-I1)") (class "Default")
      (node (ref "E13") (pin "10") (pinfunction "I1_10") (pintype "input"))
      (node (ref "E3") (pin "2") (pinfunction "O_2") (pintype "output"))
    )
    (net (code "182") (name "Net-(E13D-I0)") (class "Default")
      (node (ref "E13") (pin "12") (pinfunction "I0_12") (pintype "input"))
      (node (ref "E31") (pin "11") (pinfunction "O_11") (pintype "output"))
    )
    (net (code "183") (name "Net-(E13D-I1)") (class "Default")
      (node (ref "E13") (pin "13") (pinfunction "I1_13") (pintype "input"))
      (node (ref "E3") (pin "8") (pinfunction "O_8") (pintype "output"))
    )
    (net (code "184") (name "Net-(E16A-O)") (class "Default")
      (node (ref "E16") (pin "3") (pinfunction "O_3") (pintype "output"))
      (node (ref "E28") (pin "11") (pinfunction "I0_11") (pintype "input"))
      (node (ref "E28") (pin "12") (pinfunction "I1_12") (pintype "input"))
    )
    (net (code "185") (name "Net-(E16B-O)") (class "Default")
      (node (ref "E16") (pin "6") (pinfunction "O_6") (pintype "output"))
      (node (ref "E27") (pin "10") (pinfunction "I1_10") (pintype "input"))
    )
    (net (code "186") (name "Net-(E16D-O)") (class "Default")
      (node (ref "E16") (pin "11") (pinfunction "O_11") (pintype "output"))
      (node (ref "E20") (pin "9") (pinfunction "CLK_9") (pintype "input"))
      (node (ref "E37") (pin "9") (pinfunction "CLK_9") (pintype "input"))
      (node (ref "E6") (pin "9") (pinfunction "CLK_9") (pintype "input"))
    )
    (net (code "187") (name "Net-(E18A-I0)") (class "Default")
      (node (ref "C33") (pin "1") (pinfunction "1_1") (pintype "passive"))
      (node (ref "E18") (pin "1") (pinfunction "I0_1") (pintype "input"))
      (node (ref "E18") (pin "2") (pinfunction "I1_2") (pintype "input"))
      (node (ref "E18") (pin "4") (pinfunction "I2_4") (pintype "input"))
      (node (ref "E18") (pin "5") (pinfunction "I3_5") (pintype "input"))
      (node (ref "R4") (pin "2") (pinfunction "2_2") (pintype "passive"))
    )
    (net (code "188") (name "Net-(E18A-O)") (class "Default")
      (node (ref "E18") (pin "6") (pinfunction "O_6") (pintype "output"))
      (node (ref "E3") (pin "1") (pinfunction "I_1") (pintype "input"))
    )
    (net (code "189") (name "Net-(E18B-O)") (class "Default")
      (node (ref "E18") (pin "8") (pinfunction "O_8") (pintype "output"))
      (node (ref "E31") (pin "9") (pinfunction "I0_9") (pintype "input"))
    )
    (net (code "190") (name "Net-(E24A-I1)") (class "Default")
      (node (ref "E24") (pin "11") (pinfunction "I0_11") (pintype "input"))
      (node (ref "E24") (pin "3") (pinfunction "I1_3") (pintype "input"))
      (node (ref "E24") (pin "5") (pinfunction "I0_5") (pintype "input"))
      (node (ref "E24") (pin "9") (pinfunction "I1_9") (pintype "input"))
      (node (ref "E39") (pin "11") (pinfunction "I0_11") (pintype "input"))
      (node (ref "E39") (pin "3") (pinfunction "I1_3") (pintype "input"))
      (node (ref "E39") (pin "5") (pinfunction "I0_5") (pintype "input"))
      (node (ref "E39") (pin "9") (pinfunction "I1_9") (pintype "input"))
      (node (ref "E43") (pin "3") (pinfunction "O_3") (pintype "output"))
      (node (ref "E9") (pin "11") (pinfunction "I0_11") (pintype "input"))
      (node (ref "E9") (pin "3") (pinfunction "I1_3") (pintype "input"))
      (node (ref "E9") (pin "5") (pinfunction "I0_5") (pintype "input"))
      (node (ref "E9") (pin "9") (pinfunction "I1_9") (pintype "input"))
    )
    (net (code "191") (name "Net-(E27C-I0)") (class "Default")
      (node (ref "E27") (pin "9") (pinfunction "I0_9") (pintype "input"))
      (node (ref "E8") (pin "3") (pinfunction "O_3") (pintype "output"))
    )
    (net (code "192") (name "Net-(E27C-O)") (class "Default")
      (node (ref "E27") (pin "8") (pinfunction "O_8") (pintype "output"))
      (node (ref "E45") (pin "2") (pinfunction "I0_2") (pintype "input"))
      (node (ref "E45") (pin "3") (pinfunction "I1_3") (pintype "input"))
    )
    (net (code "193") (name "Net-(E28A-I0)") (class "Default")
      (node (ref "E28") (pin "2") (pinfunction "I0_2") (pintype "input"))
      (node (ref "E28") (pin "3") (pinfunction "I1_3") (pintype "input"))
      (node (ref "E28") (pin "5") (pinfunction "I0_5") (pintype "input"))
      (node (ref "E28") (pin "6") (pinfunction "I1_6") (pintype "input"))
      (node (ref "E43") (pin "6") (pinfunction "O_6") (pintype "output"))
    )
    (net (code "194") (name "Net-(E28C-I0)") (class "Default")
      (node (ref "E28") (pin "8") (pinfunction "I0_8") (pintype "input"))
      (node (ref "E28") (pin "9") (pinfunction "I1_9") (pintype "input"))
      (node (ref "E8") (pin "8") (pinfunction "O_8") (pintype "output"))
    )
    (net (code "195") (name "Net-(E30A-CLR)") (class "Default")
      (node (ref "E30") (pin "1") (pinfunction "CLR_1") (pintype "input"))
      (node (ref "E34") (pin "11") (pinfunction "O_11") (pintype "output"))
    )
    (net (code "196") (name "Net-(E30B-CLR)") (class "Default")
      (node (ref "E30") (pin "13") (pinfunction "CLR_13") (pintype "input"))
      (node (ref "E34") (pin "6") (pinfunction "O_6") (pintype "output"))
    )
    (net (code "197") (name "Net-(E31A-I0)") (class "Default")
      (node (ref "E31") (pin "1") (pinfunction "I0_1") (pintype "input"))
      (node (ref "R7") (pin "1") (pinfunction "1_1") (pintype "passive"))
      (node (ref "W32") (pin "2") (pinfunction "2_2") (pintype "passive"))
    )
    (net (code "198") (name "Net-(E31A-O)") (class "Default")
      (node (ref "E31") (pin "3") (pinfunction "O_3") (pintype "output"))
      (node (ref "E43") (pin "12") (pinfunction "I0_12") (pintype "input"))
      (node (ref "E43") (pin "13") (pinfunction "I1_13") (pintype "input"))
    )
    (net (code "199") (name "Net-(E31B-I0)") (class "Default")
      (node (ref "E31") (pin "4") (pinfunction "I0_4") (pintype "input"))
      (node (ref "R8") (pin "1") (pinfunction "1_1") (pintype "passive"))
      (node (ref "W31") (pin "2") (pinfunction "2_2") (pintype "passive"))
    )
    (net (code "200") (name "Net-(E31B-O)") (class "Default")
      (node (ref "E31") (pin "6") (pinfunction "O_6") (pintype "output"))
      (node (ref "E43") (pin "10") (pinfunction "I1_10") (pintype "input"))
      (node (ref "E43") (pin "9") (pinfunction "I0_9") (pintype "input"))
    )
    (net (code "201") (name "Net-(E31C-I1)") (class "Default")
      (node (ref "E31") (pin "10") (pinfunction "I1_10") (pintype "input"))
      (node (ref "R12") (pin "1") (pinfunction "1_1") (pintype "passive"))
      (node (ref "W30") (pin "2") (pinfunction "2_2") (pintype "passive"))
    )
    (net (code "202") (name "Net-(E31D-I0)") (class "Default")
      (node (ref "E31") (pin "12") (pinfunction "I0_12") (pintype "input"))
      (node (ref "E4") (pin "8") (pinfunction "O_8") (pintype "output"))
    )
    (net (code "203") (name "Net-(E31D-I1)") (class "Default")
      (node (ref "E31") (pin "13") (pinfunction "I1_13") (pintype "input"))
      (node (ref "R11") (pin "1") (pinfunction "1_1") (pintype "passive"))
      (node (ref "W29") (pin "2") (pinfunction "2_2") (pintype "passive"))
    )
    (net (code "204") (name "Net-(E42A-I0)") (class "Default")
      (node (ref "E42") (pin "1") (pinfunction "I0_1") (pintype "input"))
      (node (ref "E42") (pin "2") (pinfunction "I1_2") (pintype "input"))
      (node (ref "E44") (pin "4") (pinfunction "~{Q}_4") (pintype "output"))
    )
    (net (code "205") (name "Net-(E42B-I0)") (class "Default")
      (node (ref "E42") (pin "4") (pinfunction "I0_4") (pintype "input"))
      (node (ref "E42") (pin "5") (pinfunction "I1_5") (pintype "input"))
      (node (ref "E44") (pin "5") (pinfunction "Q_5") (pintype "output"))
    )
    (net (code "206") (name "Net-(E42C-I0)") (class "Default")
      (node (ref "E42") (pin "10") (pinfunction "I1_10") (pintype "input"))
      (node (ref "E42") (pin "9") (pinfunction "I0_9") (pintype "input"))
      (node (ref "E44") (pin "13") (pinfunction "Q_13") (pintype "output"))
    )
    (net (code "207") (name "Net-(E42D-I0)") (class "Default")
      (node (ref "E42") (pin "12") (pinfunction "I0_12") (pintype "input"))
      (node (ref "E42") (pin "13") (pinfunction "I1_13") (pintype "input"))
      (node (ref "E44") (pin "12") (pinfunction "~{Q}_12") (pintype "output"))
    )
    (net (code "208") (name "Net-(E44A-C)") (class "Default")
      (node (ref "E44") (pin "14") (pinfunction "C_14") (pintype "input"))
      (node (ref "W27") (pin "2") (pinfunction "2_2") (pintype "passive"))
    )
    (net (code "209") (name "Net-(E44A-R{slash}C)") (class "Default")
      (node (ref "E44") (pin "15") (pinfunction "R/C_15") (pintype "input"))
      (node (ref "R21") (pin "2") (pinfunction "2_2") (pintype "passive"))
      (node (ref "W27") (pin "1") (pinfunction "1_1") (pintype "passive"))
    )
    (net (code "210") (name "Net-(E44B-C)") (class "Default")
      (node (ref "E44") (pin "6") (pinfunction "C_6") (pintype "input"))
      (node (ref "W25") (pin "2") (pinfunction "2_2") (pintype "passive"))
    )
    (net (code "211") (name "Net-(E44B-R{slash}C)") (class "Default")
      (node (ref "E44") (pin "7") (pinfunction "R/C_7") (pintype "input"))
      (node (ref "R22") (pin "2") (pinfunction "2_2") (pintype "passive"))
      (node (ref "W25") (pin "1") (pinfunction "1_1") (pintype "passive"))
    )
    (net (code "212") (name "Net-(R23-A)") (class "Default")
      (node (ref "R21") (pin "1") (pinfunction "1_1") (pintype "passive"))
      (node (ref "R23") (pin "1") (pinfunction "A_1") (pintype "passive"))
      (node (ref "W28") (pin "1") (pinfunction "1_1") (pintype "passive"))
    )
    (net (code "213") (name "Net-(R24-A)") (class "Default")
      (node (ref "R22") (pin "1") (pinfunction "1_1") (pintype "passive"))
      (node (ref "R24") (pin "1") (pinfunction "A_1") (pintype "passive"))
      (node (ref "W26") (pin "1") (pinfunction "1_1") (pintype "passive"))
    )
    (net (code "214") (name "TP3") (class "Default")
      (node (ref "E32") (pin "5") (pinfunction "Y3_5") (pintype "input"))
      (node (ref "U$2") (pin "CH2") (pinfunction "1_CH2") (pintype "bidirectional"))
    )
    (net (code "215") (name "TP3L") (class "Default")
      (node (ref "E16") (pin "10") (pinfunction "I1_10") (pintype "input"))
      (node (ref "E16") (pin "12") (pinfunction "I0_12") (pintype "input"))
      (node (ref "E32") (pin "6") (pinfunction "A3_6") (pintype "output"))
    )
    (net (code "216") (name "VCC") (class "Default")
      (node (ref "C1") (pin "1") (pinfunction "1_1") (pintype "passive"))
      (node (ref "C10") (pin "1") (pinfunction "1_1") (pintype "passive"))
      (node (ref "C100") (pin "+") (pinfunction "+_+") (pintype "passive"))
      (node (ref "C101") (pin "+") (pinfunction "+_+") (pintype "passive"))
      (node (ref "C102") (pin "+") (pinfunction "+_+") (pintype "passive"))
      (node (ref "C11") (pin "1") (pinfunction "1_1") (pintype "passive"))
      (node (ref "C12") (pin "1") (pinfunction "1_1") (pintype "passive"))
      (node (ref "C13") (pin "1") (pinfunction "1_1") (pintype "passive"))
      (node (ref "C14") (pin "1") (pinfunction "1_1") (pintype "passive"))
      (node (ref "C15") (pin "1") (pinfunction "1_1") (pintype "passive"))
      (node (ref "C16") (pin "1") (pinfunction "1_1") (pintype "passive"))
      (node (ref "C17") (pin "1") (pinfunction "1_1") (pintype "passive"))
      (node (ref "C18") (pin "1") (pinfunction "1_1") (pintype "passive"))
      (node (ref "C19") (pin "1") (pinfunction "1_1") (pintype "passive"))
      (node (ref "C2") (pin "1") (pinfunction "1_1") (pintype "passive"))
      (node (ref "C20") (pin "1") (pinfunction "1_1") (pintype "passive"))
      (node (ref "C21") (pin "1") (pinfunction "1_1") (pintype "passive"))
      (node (ref "C22") (pin "1") (pinfunction "1_1") (pintype "passive"))
      (node (ref "C23") (pin "1") (pinfunction "1_1") (pintype "passive"))
      (node (ref "C24") (pin "1") (pinfunction "1_1") (pintype "passive"))
      (node (ref "C25") (pin "1") (pinfunction "1_1") (pintype "passive"))
      (node (ref "C26") (pin "1") (pinfunction "1_1") (pintype "passive"))
      (node (ref "C27") (pin "1") (pinfunction "1_1") (pintype "passive"))
      (node (ref "C28") (pin "1") (pinfunction "1_1") (pintype "passive"))
      (node (ref "C29") (pin "1") (pinfunction "1_1") (pintype "passive"))
      (node (ref "C3") (pin "1") (pinfunction "1_1") (pintype "passive"))
      (node (ref "C30") (pin "1") (pinfunction "1_1") (pintype "passive"))
      (node (ref "C31") (pin "1") (pinfunction "1_1") (pintype "passive"))
      (node (ref "C32") (pin "1") (pinfunction "1_1") (pintype "passive"))
      (node (ref "C4") (pin "1") (pinfunction "1_1") (pintype "passive"))
      (node (ref "C5") (pin "1") (pinfunction "1_1") (pintype "passive"))
      (node (ref "C6") (pin "1") (pinfunction "1_1") (pintype "passive"))
      (node (ref "C7") (pin "1") (pinfunction "1_1") (pintype "passive"))
      (node (ref "C8") (pin "1") (pinfunction "1_1") (pintype "passive"))
      (node (ref "C9") (pin "1") (pinfunction "1_1") (pintype "passive"))
      (node (ref "R1") (pin "2") (pinfunction "2_2") (pintype "passive"))
      (node (ref "R10") (pin "2") (pinfunction "2_2") (pintype "passive"))
      (node (ref "R11") (pin "2") (pinfunction "2_2") (pintype "passive"))
      (node (ref "R12") (pin "2") (pinfunction "2_2") (pintype "passive"))
      (node (ref "R13") (pin "2") (pinfunction "2_2") (pintype "passive"))
      (node (ref "R15") (pin "2") (pinfunction "2_2") (pintype "passive"))
      (node (ref "R17") (pin "2") (pinfunction "2_2") (pintype "passive"))
      (node (ref "R19") (pin "2") (pinfunction "2_2") (pintype "passive"))
      (node (ref "R23") (pin "2") (pinfunction "S_2") (pintype "passive"))
      (node (ref "R23") (pin "3") (pinfunction "E_3") (pintype "passive"))
      (node (ref "R24") (pin "2") (pinfunction "S_2") (pintype "passive"))
      (node (ref "R24") (pin "3") (pinfunction "E_3") (pintype "passive"))
      (node (ref "R3") (pin "2") (pinfunction "2_2") (pintype "passive"))
      (node (ref "R5") (pin "2") (pinfunction "2_2") (pintype "passive"))
      (node (ref "R7") (pin "2") (pinfunction "2_2") (pintype "passive"))
      (node (ref "R8") (pin "2") (pinfunction "2_2") (pintype "passive"))
      (node (ref "R9") (pin "2") (pinfunction "2_2") (pintype "passive"))
      (node (ref "U$2") (pin "AA2") (pinfunction "1_AA2") (pintype "bidirectional"))
      (node (ref "U$2") (pin "BA2") (pinfunction "1_BA2") (pintype "bidirectional"))
      (node (ref "U$2") (pin "CA2") (pinfunction "1_CA2") (pintype "bidirectional"))
      (node (ref "W26") (pin "2") (pinfunction "2_2") (pintype "passive"))
      (node (ref "W28") (pin "2") (pinfunction "2_2") (pintype "passive"))
    )
    (net (code "217") (name "unconnected-(E29A-O8-Pad10)") (class "Default")
      (node (ref "E29") (pin "10") (pinfunction "O8_10") (pintype "output"))
    )
    (net (code "218") (name "unconnected-(E29A-O9-Pad11)") (class "Default")
      (node (ref "E29") (pin "11") (pinfunction "O9_11") (pintype "output"))
    )
    (net (code "219") (name "unconnected-(E30A-~{Q}-Pad6)") (class "Default")
      (node (ref "E30") (pin "6") (pinfunction "~{Q}_6") (pintype "output"))
    )
    (net (code "220") (name "unconnected-(E30B-~{Q}-Pad8)") (class "Default")
      (node (ref "E30") (pin "8") (pinfunction "~{Q}_8") (pintype "output"))
    )
    (net (code "221") (name "unconnected-(E33A-O8-Pad10)") (class "Default")
      (node (ref "E33") (pin "10") (pinfunction "O8_10") (pintype "output"))
    )
    (net (code "222") (name "unconnected-(E33A-O9-Pad11)") (class "Default")
      (node (ref "E33") (pin "11") (pinfunction "O9_11") (pintype "output"))
    )
    (net (code "223") (name "unconnected-(E35A-~{Q}-Pad6)") (class "Default")
      (node (ref "E35") (pin "6") (pinfunction "~{Q}_6") (pintype "output"))
    )
    (net (code "224") (name "unconnected-(E35B-~{Q}-Pad8)") (class "Default")
      (node (ref "E35") (pin "8") (pinfunction "~{Q}_8") (pintype "output"))
    )
    (net (code "225") (name "~{C0}") (class "Default")
      (node (ref "E28") (pin "4") (pinfunction "O_4") (pintype "open_collector"))
      (node (ref "U$2") (pin "CE1") (pinfunction "1_CE1") (pintype "bidirectional"))
    )
    (net (code "226") (name "~{C1}") (class "Default")
      (node (ref "E28") (pin "1") (pinfunction "O_1") (pintype "open_collector"))
      (node (ref "U$2") (pin "CH1") (pinfunction "1_CH1") (pintype "bidirectional"))
    )
    (net (code "227") (name "~{DATA0}") (class "Default")
      (node (ref "E5") (pin "12") (pinfunction "B1_12") (pintype "bidirectional"))
      (node (ref "E9") (pin "10") (pinfunction "O_10") (pintype "open_collector"))
      (node (ref "U$2") (pin "AR1") (pinfunction "1_AR1") (pintype "bidirectional"))
    )
    (net (code "228") (name "~{DATA1}") (class "Default")
      (node (ref "E5") (pin "15") (pinfunction "B0_15") (pintype "bidirectional"))
      (node (ref "E9") (pin "13") (pinfunction "O_13") (pintype "open_collector"))
      (node (ref "U$2") (pin "AS1") (pinfunction "1_AS1") (pintype "bidirectional"))
    )
    (net (code "229") (name "~{DATA2}") (class "Default")
      (node (ref "E5") (pin "4") (pinfunction "B3_4") (pintype "bidirectional"))
      (node (ref "E9") (pin "4") (pinfunction "O_4") (pintype "open_collector"))
      (node (ref "U$2") (pin "AU1") (pinfunction "1_AU1") (pintype "bidirectional"))
    )
    (net (code "230") (name "~{DATA3}") (class "Default")
      (node (ref "E5") (pin "1") (pinfunction "B2_1") (pintype "bidirectional"))
      (node (ref "E9") (pin "1") (pinfunction "O_1") (pintype "open_collector"))
      (node (ref "U$2") (pin "AV1") (pinfunction "1_AV1") (pintype "bidirectional"))
    )
    (net (code "231") (name "~{DATA4}") (class "Default")
      (node (ref "E19") (pin "12") (pinfunction "B1_12") (pintype "bidirectional"))
      (node (ref "E24") (pin "10") (pinfunction "O_10") (pintype "open_collector"))
      (node (ref "U$2") (pin "BR1") (pinfunction "1_BR1") (pintype "bidirectional"))
    )
    (net (code "232") (name "~{DATA5}") (class "Default")
      (node (ref "E19") (pin "15") (pinfunction "B0_15") (pintype "bidirectional"))
      (node (ref "E24") (pin "13") (pinfunction "O_13") (pintype "open_collector"))
      (node (ref "U$2") (pin "BS1") (pinfunction "1_BS1") (pintype "bidirectional"))
    )
    (net (code "233") (name "~{DATA6}") (class "Default")
      (node (ref "E19") (pin "4") (pinfunction "B3_4") (pintype "bidirectional"))
      (node (ref "E24") (pin "4") (pinfunction "O_4") (pintype "open_collector"))
      (node (ref "U$2") (pin "BU1") (pinfunction "1_BU1") (pintype "bidirectional"))
    )
    (net (code "234") (name "~{DATA7}") (class "Default")
      (node (ref "E19") (pin "1") (pinfunction "B2_1") (pintype "bidirectional"))
      (node (ref "E24") (pin "1") (pinfunction "O_1") (pintype "open_collector"))
      (node (ref "U$2") (pin "BV1") (pinfunction "1_BV1") (pintype "bidirectional"))
    )
    (net (code "235") (name "~{DATA8}") (class "Default")
      (node (ref "E36") (pin "12") (pinfunction "B1_12") (pintype "bidirectional"))
      (node (ref "E39") (pin "10") (pinfunction "O_10") (pintype "open_collector"))
      (node (ref "U$2") (pin "DR1") (pinfunction "1_DR1") (pintype "bidirectional"))
    )
    (net (code "236") (name "~{DATA9}") (class "Default")
      (node (ref "E36") (pin "15") (pinfunction "B0_15") (pintype "bidirectional"))
      (node (ref "E39") (pin "13") (pinfunction "O_13") (pintype "open_collector"))
      (node (ref "U$2") (pin "DS1") (pinfunction "1_DS1") (pintype "bidirectional"))
    )
    (net (code "237") (name "~{DATA10}") (class "Default")
      (node (ref "E36") (pin "4") (pinfunction "B3_4") (pintype "bidirectional"))
      (node (ref "E39") (pin "4") (pinfunction "O_4") (pintype "open_collector"))
      (node (ref "U$2") (pin "DU1") (pinfunction "1_DU1") (pintype "bidirectional"))
    )
    (net (code "238") (name "~{DATA11}") (class "Default")
      (node (ref "E36") (pin "1") (pinfunction "B2_1") (pintype "bidirectional"))
      (node (ref "E39") (pin "1") (pinfunction "O_1") (pintype "open_collector"))
      (node (ref "U$2") (pin "DV1") (pinfunction "1_DV1") (pintype "bidirectional"))
    )
    (net (code "239") (name "~{INTERNAL_IO}") (class "Default")
      (node (ref "E28") (pin "13") (pinfunction "O_13") (pintype "open_collector"))
      (node (ref "U$2") (pin "CL1") (pinfunction "1_CL1") (pintype "bidirectional"))
    )
    (net (code "240") (name "~{INT_RQST}") (class "Default")
      (node (ref "E45") (pin "1") (pinfunction "O_1") (pintype "open_collector"))
      (node (ref "U$2") (pin "CP1") (pinfunction "1_CP1") (pintype "bidirectional"))
    )
    (net (code "241") (name "~{IO_PAUSE}") (class "Default")
      (node (ref "E14") (pin "1") (pinfunction "Y1_1") (pintype "input"))
      (node (ref "U$2") (pin "CD1") (pinfunction "1_CD1") (pintype "bidirectional"))
    )
    (net (code "242") (name "~{MD03}") (class "Default")
      (node (ref "E14") (pin "11") (pinfunction "Y1_11") (pintype "input"))
      (node (ref "U$2") (pin "AP1") (pinfunction "1_AP1") (pintype "bidirectional"))
    )
    (net (code "243") (name "~{MD04}") (class "Default")
      (node (ref "E14") (pin "5") (pinfunction "Y3_5") (pintype "input"))
      (node (ref "U$2") (pin "BK1") (pinfunction "1_BK1") (pintype "bidirectional"))
    )
    (net (code "244") (name "~{MD05}") (class "Default")
      (node (ref "E14") (pin "3") (pinfunction "Y2_3") (pintype "input"))
      (node (ref "U$2") (pin "BL1") (pinfunction "1_BL1") (pintype "bidirectional"))
    )
    (net (code "245") (name "~{MD06}") (class "Default")
      (node (ref "E14") (pin "13") (pinfunction "Y2_13") (pintype "input"))
      (node (ref "U$2") (pin "BM1") (pinfunction "1_BM1") (pintype "bidirectional"))
    )
    (net (code "246") (name "~{MD07}") (class "Default")
      (node (ref "E14") (pin "15") (pinfunction "Y3_15") (pintype "input"))
      (node (ref "U$2") (pin "BP1") (pinfunction "1_BP1") (pintype "bidirectional"))
    )
    (net (code "247") (name "~{MD08}") (class "Default")
      (node (ref "E32") (pin "1") (pinfunction "Y1_1") (pintype "input"))
      (node (ref "U$2") (pin "DK1") (pinfunction "1_DK1") (pintype "bidirectional"))
    )
    (net (code "248") (name "~{MD09}") (class "Default")
      (node (ref "E32") (pin "15") (pinfunction "Y3_15") (pintype "input"))
      (node (ref "U$2") (pin "DL1") (pinfunction "1_DL1") (pintype "bidirectional"))
    )
    (net (code "249") (name "~{MD10}") (class "Default")
      (node (ref "E32") (pin "13") (pinfunction "Y2_13") (pintype "input"))
      (node (ref "U$2") (pin "DM1") (pinfunction "1_DM1") (pintype "bidirectional"))
    )
    (net (code "250") (name "~{MD11}") (class "Default")
      (node (ref "E32") (pin "11") (pinfunction "Y1_11") (pintype "input"))
      (node (ref "U$2") (pin "DP1") (pinfunction "1_DP1") (pintype "bidirectional"))
    )
    (net (code "251") (name "~{SKIP}") (class "Default")
      (node (ref "E28") (pin "10") (pinfunction "O_10") (pintype "open_collector"))
      (node (ref "U$2") (pin "CS1") (pinfunction "1_CS1") (pintype "bidirectional"))
    )
  )
)
